# Dx32_V1_1.net
KiCad netlist of a schematic drawn in EAGLE
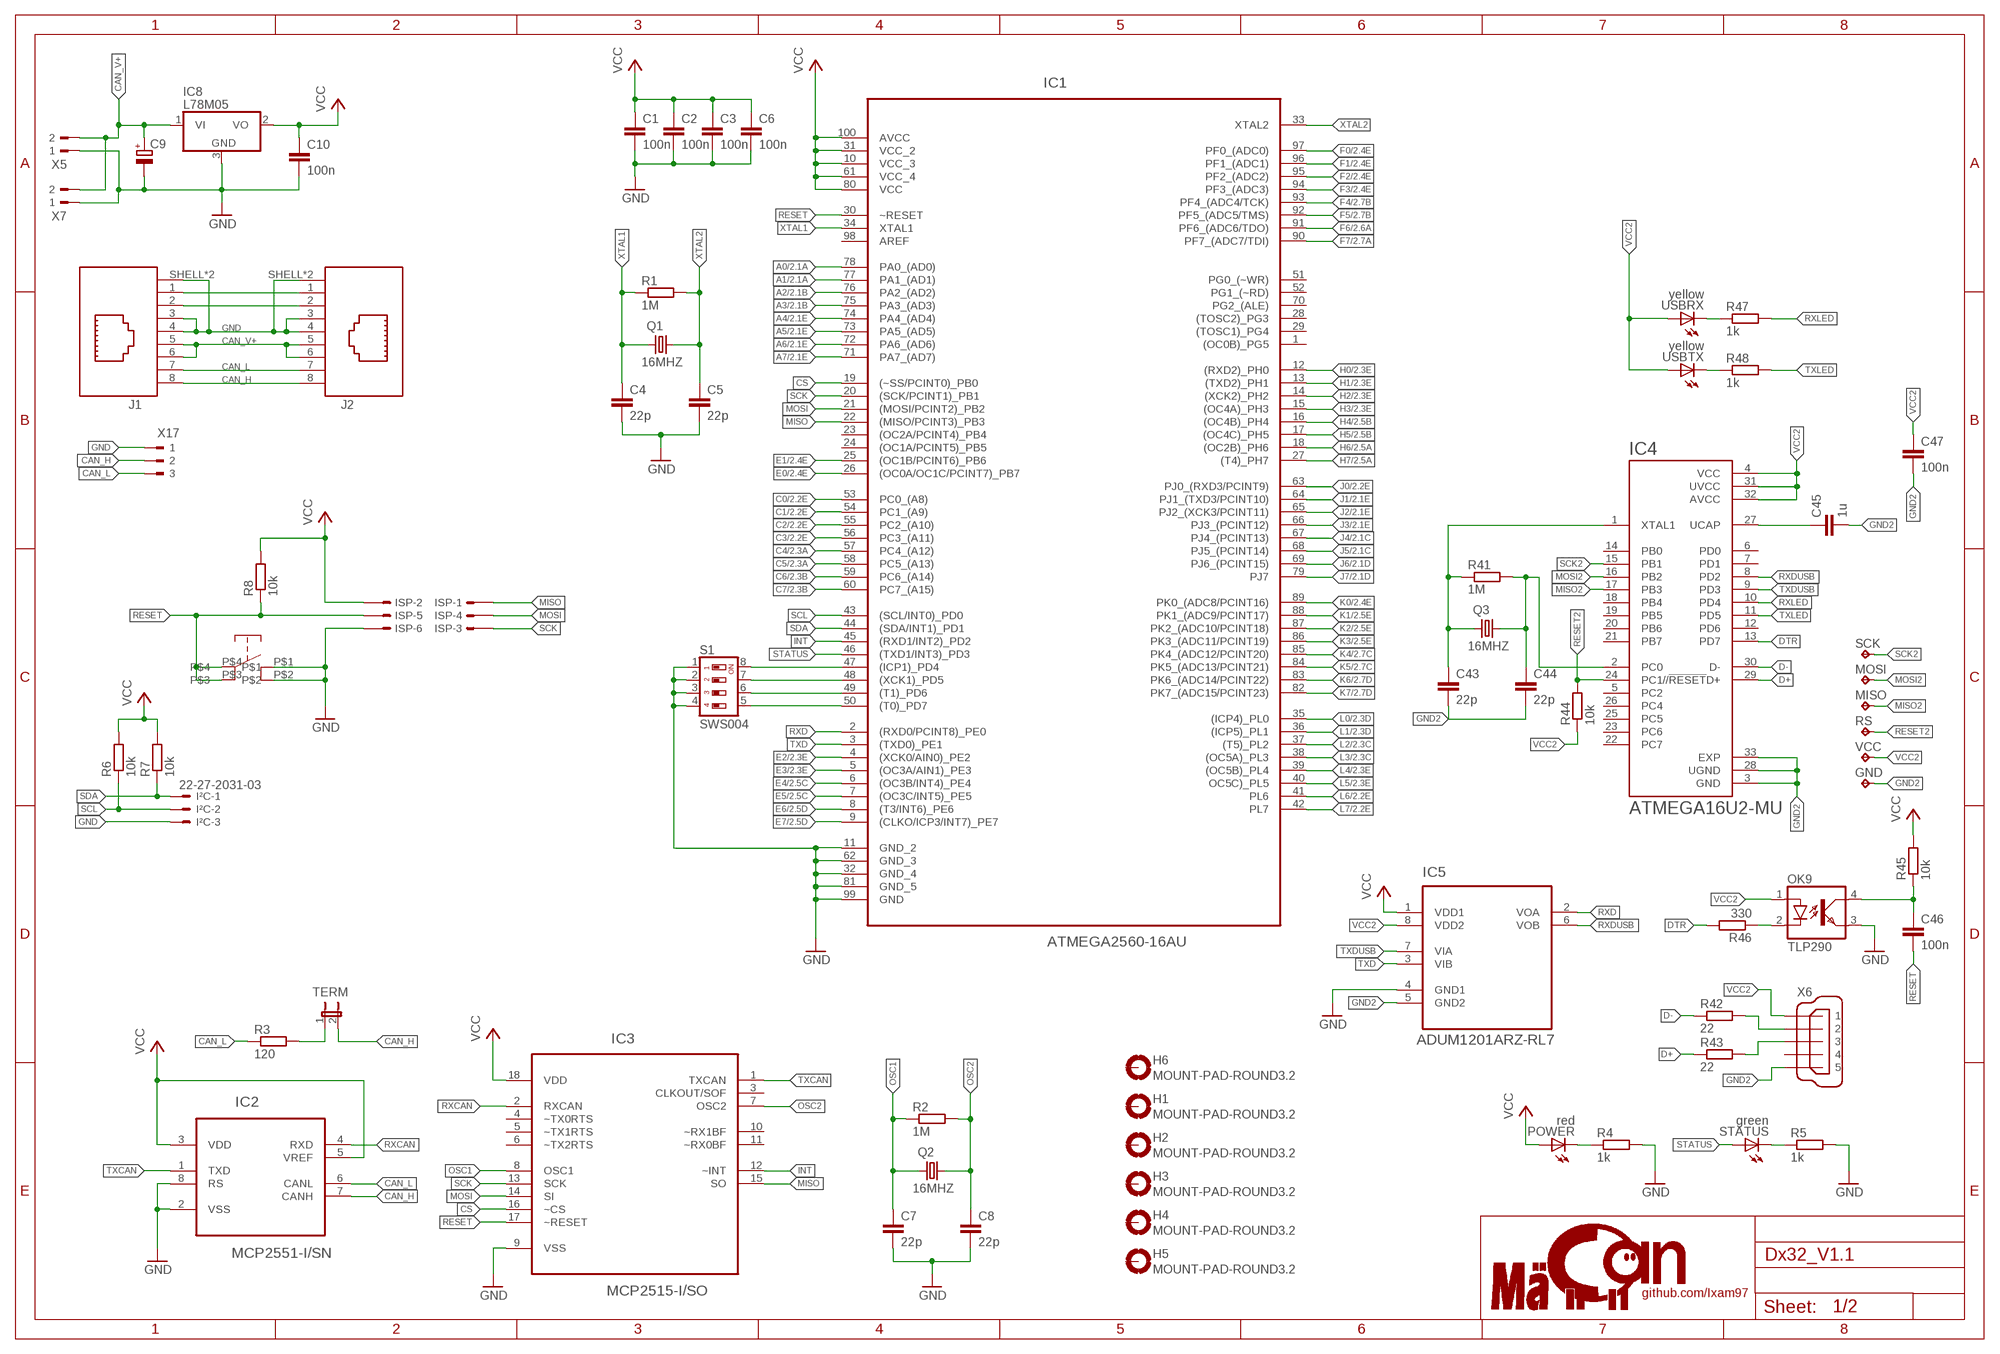
[diagram p0: schematic, sheet 1]
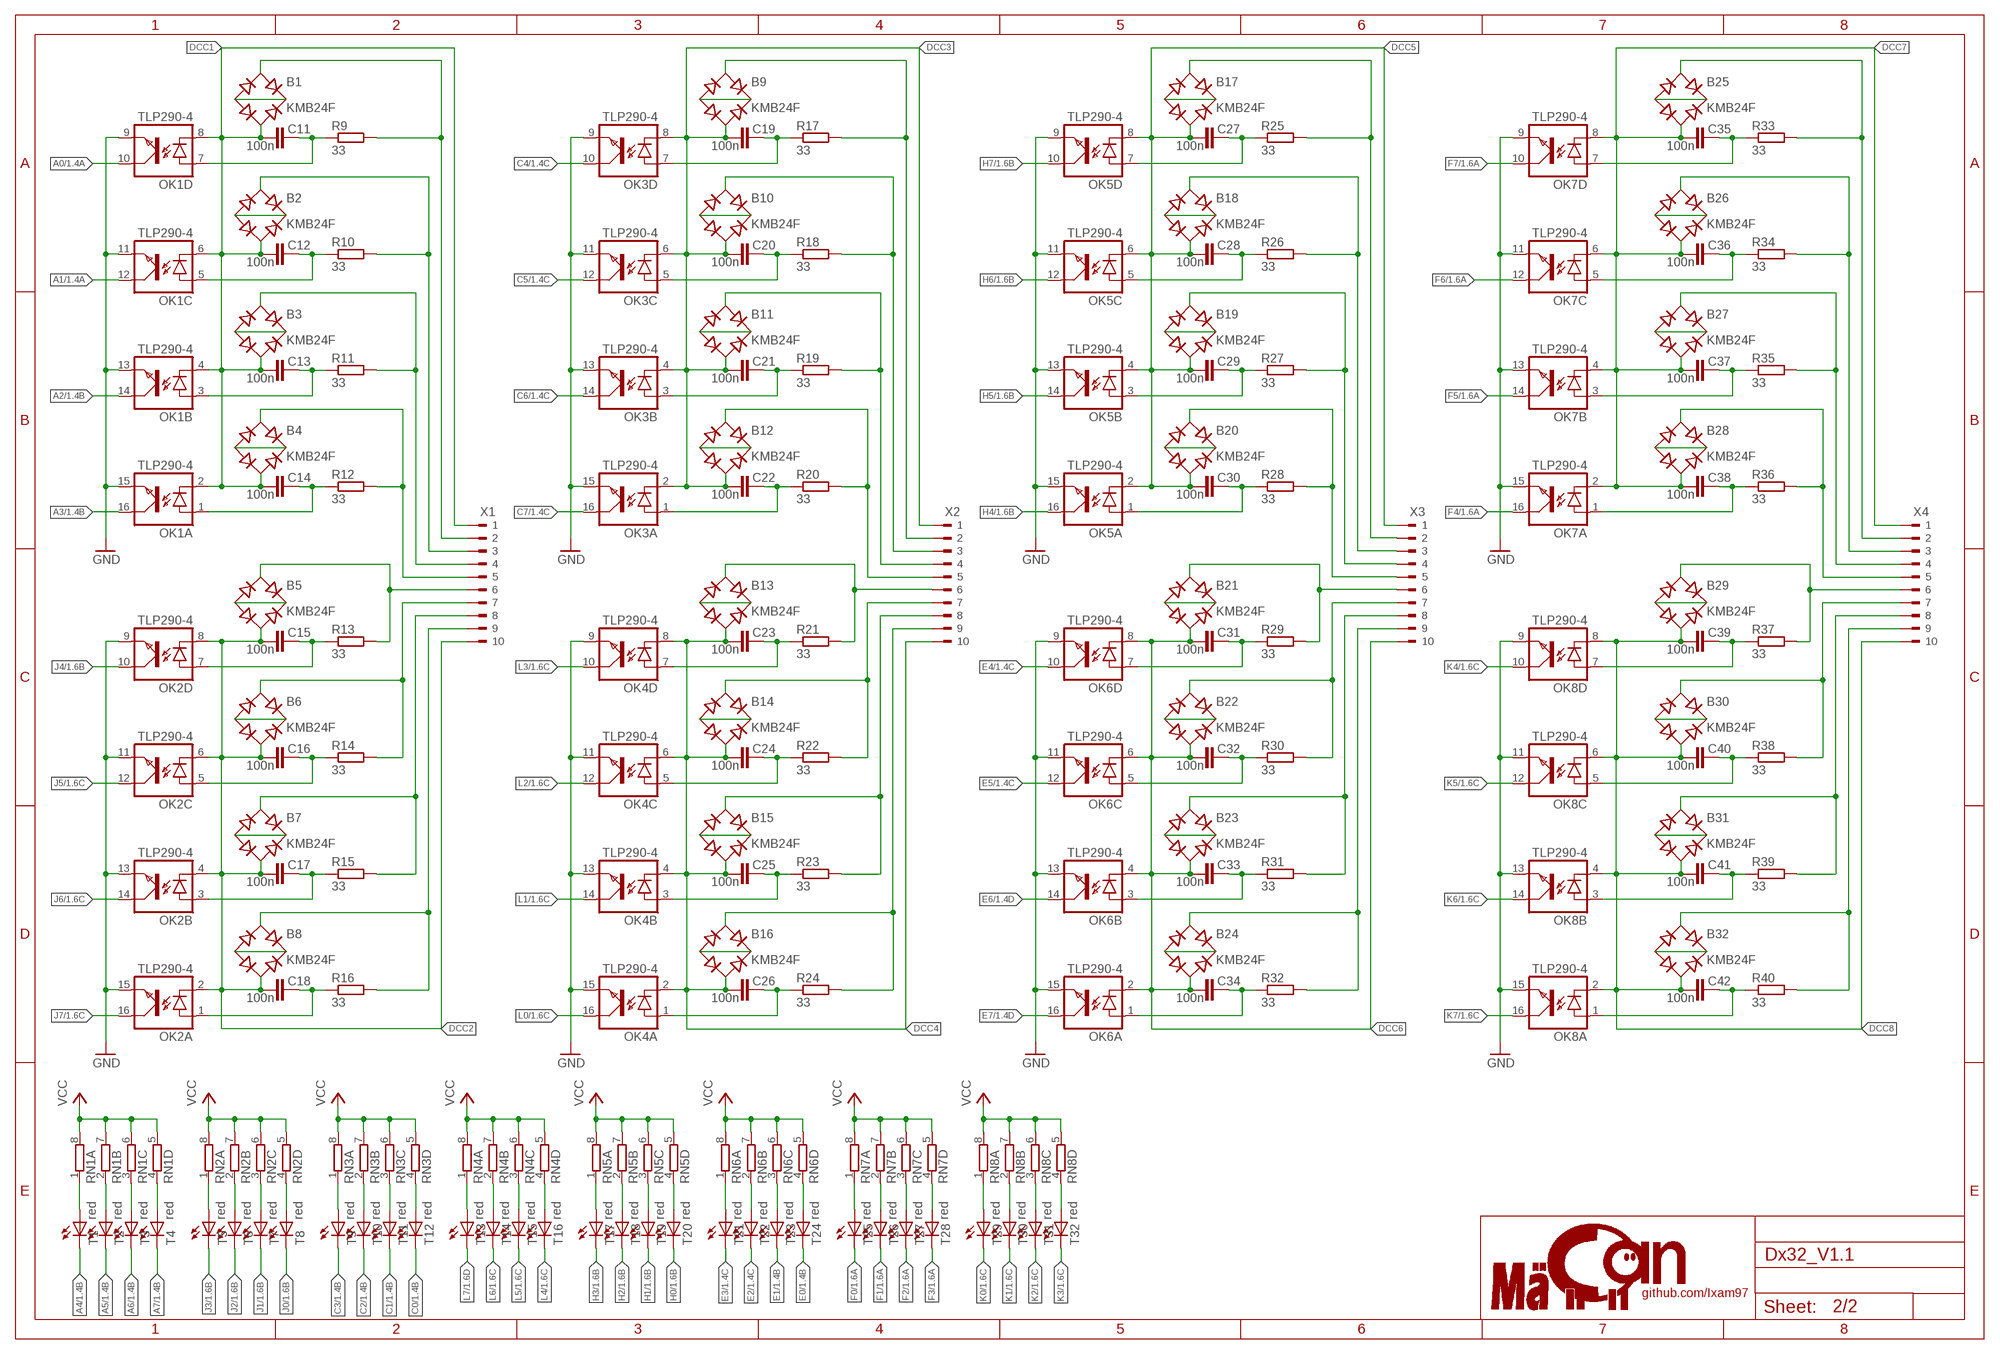
[diagram p1: schematic, sheet 2]

(export (version "E")
  (design (tool "Eeschema 10.0.6"))
  (components
    (comp (ref "B1")
      (value "KMB24F")
      (footprint "eagle-import:MBS")
      (fields (field (name "JLCPCB-PART") "C113927"))
      (libsource (lib "eagle-import") (part "BS2"))
    )
    (comp (ref "B2")
      (value "KMB24F")
      (footprint "eagle-import:MBS")
      (libsource (lib "eagle-import") (part "BS2"))
    )
    (comp (ref "B3")
      (value "KMB24F")
      (footprint "eagle-import:MBS")
      (libsource (lib "eagle-import") (part "BS2"))
    )
    (comp (ref "B4")
      (value "KMB24F")
      (footprint "eagle-import:MBS")
      (libsource (lib "eagle-import") (part "BS2"))
    )
    (comp (ref "B5")
      (value "KMB24F")
      (footprint "eagle-import:MBS")
      (libsource (lib "eagle-import") (part "BS2"))
    )
    (comp (ref "B6")
      (value "KMB24F")
      (footprint "eagle-import:MBS")
      (libsource (lib "eagle-import") (part "BS2"))
    )
    (comp (ref "B7")
      (value "KMB24F")
      (footprint "eagle-import:MBS")
      (libsource (lib "eagle-import") (part "BS2"))
    )
    (comp (ref "B8")
      (value "KMB24F")
      (footprint "eagle-import:MBS")
      (libsource (lib "eagle-import") (part "BS2"))
    )
    (comp (ref "B9")
      (value "KMB24F")
      (footprint "eagle-import:MBS")
      (libsource (lib "eagle-import") (part "BS2"))
    )
    (comp (ref "B10")
      (value "KMB24F")
      (footprint "eagle-import:MBS")
      (libsource (lib "eagle-import") (part "BS2"))
    )
    (comp (ref "B11")
      (value "KMB24F")
      (footprint "eagle-import:MBS")
      (libsource (lib "eagle-import") (part "BS2"))
    )
    (comp (ref "B12")
      (value "KMB24F")
      (footprint "eagle-import:MBS")
      (libsource (lib "eagle-import") (part "BS2"))
    )
    (comp (ref "B13")
      (value "KMB24F")
      (footprint "eagle-import:MBS")
      (libsource (lib "eagle-import") (part "BS2"))
    )
    (comp (ref "B14")
      (value "KMB24F")
      (footprint "eagle-import:MBS")
      (libsource (lib "eagle-import") (part "BS2"))
    )
    (comp (ref "B15")
      (value "KMB24F")
      (footprint "eagle-import:MBS")
      (libsource (lib "eagle-import") (part "BS2"))
    )
    (comp (ref "B16")
      (value "KMB24F")
      (footprint "eagle-import:MBS")
      (libsource (lib "eagle-import") (part "BS2"))
    )
    (comp (ref "B17")
      (value "KMB24F")
      (footprint "eagle-import:MBS")
      (libsource (lib "eagle-import") (part "BS2"))
    )
    (comp (ref "B18")
      (value "KMB24F")
      (footprint "eagle-import:MBS")
      (libsource (lib "eagle-import") (part "BS2"))
    )
    (comp (ref "B19")
      (value "KMB24F")
      (footprint "eagle-import:MBS")
      (libsource (lib "eagle-import") (part "BS2"))
    )
    (comp (ref "B20")
      (value "KMB24F")
      (footprint "eagle-import:MBS")
      (libsource (lib "eagle-import") (part "BS2"))
    )
    (comp (ref "B21")
      (value "KMB24F")
      (footprint "eagle-import:MBS")
      (libsource (lib "eagle-import") (part "BS2"))
    )
    (comp (ref "B22")
      (value "KMB24F")
      (footprint "eagle-import:MBS")
      (libsource (lib "eagle-import") (part "BS2"))
    )
    (comp (ref "B23")
      (value "KMB24F")
      (footprint "eagle-import:MBS")
      (libsource (lib "eagle-import") (part "BS2"))
    )
    (comp (ref "B24")
      (value "KMB24F")
      (footprint "eagle-import:MBS")
      (libsource (lib "eagle-import") (part "BS2"))
    )
    (comp (ref "B25")
      (value "KMB24F")
      (footprint "eagle-import:MBS")
      (libsource (lib "eagle-import") (part "BS2"))
    )
    (comp (ref "B26")
      (value "KMB24F")
      (footprint "eagle-import:MBS")
      (libsource (lib "eagle-import") (part "BS2"))
    )
    (comp (ref "B27")
      (value "KMB24F")
      (footprint "eagle-import:MBS")
      (libsource (lib "eagle-import") (part "BS2"))
    )
    (comp (ref "B28")
      (value "KMB24F")
      (footprint "eagle-import:MBS")
      (libsource (lib "eagle-import") (part "BS2"))
    )
    (comp (ref "B29")
      (value "KMB24F")
      (footprint "eagle-import:MBS")
      (libsource (lib "eagle-import") (part "BS2"))
    )
    (comp (ref "B30")
      (value "KMB24F")
      (footprint "eagle-import:MBS")
      (libsource (lib "eagle-import") (part "BS2"))
    )
    (comp (ref "B31")
      (value "KMB24F")
      (footprint "eagle-import:MBS")
      (libsource (lib "eagle-import") (part "BS2"))
    )
    (comp (ref "B32")
      (value "KMB24F")
      (footprint "eagle-import:MBS")
      (libsource (lib "eagle-import") (part "BS2"))
    )
    (comp (ref "C11")
      (value "100n")
      (footprint "eagle-import:C0402")
      (libsource (lib "eagle-import") (part "C-EUC0402"))
    )
    (comp (ref "C12")
      (value "100n")
      (footprint "eagle-import:C0402")
      (libsource (lib "eagle-import") (part "C-EUC0402"))
    )
    (comp (ref "C13")
      (value "100n")
      (footprint "eagle-import:C0402")
      (libsource (lib "eagle-import") (part "C-EUC0402"))
    )
    (comp (ref "C14")
      (value "100n")
      (footprint "eagle-import:C0402")
      (libsource (lib "eagle-import") (part "C-EUC0402"))
    )
    (comp (ref "C15")
      (value "100n")
      (footprint "eagle-import:C0402")
      (libsource (lib "eagle-import") (part "C-EUC0402"))
    )
    (comp (ref "C16")
      (value "100n")
      (footprint "eagle-import:C0402")
      (libsource (lib "eagle-import") (part "C-EUC0402"))
    )
    (comp (ref "C17")
      (value "100n")
      (footprint "eagle-import:C0402")
      (libsource (lib "eagle-import") (part "C-EUC0402"))
    )
    (comp (ref "C18")
      (value "100n")
      (footprint "eagle-import:C0402")
      (libsource (lib "eagle-import") (part "C-EUC0402"))
    )
    (comp (ref "C19")
      (value "100n")
      (footprint "eagle-import:C0402")
      (libsource (lib "eagle-import") (part "C-EUC0402"))
    )
    (comp (ref "C20")
      (value "100n")
      (footprint "eagle-import:C0402")
      (libsource (lib "eagle-import") (part "C-EUC0402"))
    )
    (comp (ref "C21")
      (value "100n")
      (footprint "eagle-import:C0402")
      (libsource (lib "eagle-import") (part "C-EUC0402"))
    )
    (comp (ref "C22")
      (value "100n")
      (footprint "eagle-import:C0402")
      (libsource (lib "eagle-import") (part "C-EUC0402"))
    )
    (comp (ref "C23")
      (value "100n")
      (footprint "eagle-import:C0402")
      (libsource (lib "eagle-import") (part "C-EUC0402"))
    )
    (comp (ref "C24")
      (value "100n")
      (footprint "eagle-import:C0402")
      (libsource (lib "eagle-import") (part "C-EUC0402"))
    )
    (comp (ref "C25")
      (value "100n")
      (footprint "eagle-import:C0402")
      (libsource (lib "eagle-import") (part "C-EUC0402"))
    )
    (comp (ref "C26")
      (value "100n")
      (footprint "eagle-import:C0402")
      (libsource (lib "eagle-import") (part "C-EUC0402"))
    )
    (comp (ref "C27")
      (value "100n")
      (footprint "eagle-import:C0402")
      (libsource (lib "eagle-import") (part "C-EUC0402"))
    )
    (comp (ref "C28")
      (value "100n")
      (footprint "eagle-import:C0402")
      (libsource (lib "eagle-import") (part "C-EUC0402"))
    )
    (comp (ref "C29")
      (value "100n")
      (footprint "eagle-import:C0402")
      (libsource (lib "eagle-import") (part "C-EUC0402"))
    )
    (comp (ref "C30")
      (value "100n")
      (footprint "eagle-import:C0402")
      (libsource (lib "eagle-import") (part "C-EUC0402"))
    )
    (comp (ref "C31")
      (value "100n")
      (footprint "eagle-import:C0402")
      (libsource (lib "eagle-import") (part "C-EUC0402"))
    )
    (comp (ref "C32")
      (value "100n")
      (footprint "eagle-import:C0402")
      (libsource (lib "eagle-import") (part "C-EUC0402"))
    )
    (comp (ref "C33")
      (value "100n")
      (footprint "eagle-import:C0402")
      (libsource (lib "eagle-import") (part "C-EUC0402"))
    )
    (comp (ref "C34")
      (value "100n")
      (footprint "eagle-import:C0402")
      (libsource (lib "eagle-import") (part "C-EUC0402"))
    )
    (comp (ref "C35")
      (value "100n")
      (footprint "eagle-import:C0402")
      (libsource (lib "eagle-import") (part "C-EUC0402"))
    )
    (comp (ref "C36")
      (value "100n")
      (footprint "eagle-import:C0402")
      (libsource (lib "eagle-import") (part "C-EUC0402"))
    )
    (comp (ref "C37")
      (value "100n")
      (footprint "eagle-import:C0402")
      (libsource (lib "eagle-import") (part "C-EUC0402"))
    )
    (comp (ref "C38")
      (value "100n")
      (footprint "eagle-import:C0402")
      (libsource (lib "eagle-import") (part "C-EUC0402"))
    )
    (comp (ref "C39")
      (value "100n")
      (footprint "eagle-import:C0402")
      (libsource (lib "eagle-import") (part "C-EUC0402"))
    )
    (comp (ref "C40")
      (value "100n")
      (footprint "eagle-import:C0402")
      (libsource (lib "eagle-import") (part "C-EUC0402"))
    )
    (comp (ref "C41")
      (value "100n")
      (footprint "eagle-import:C0402")
      (libsource (lib "eagle-import") (part "C-EUC0402"))
    )
    (comp (ref "C42")
      (value "100n")
      (footprint "eagle-import:C0402")
      (libsource (lib "eagle-import") (part "C-EUC0402"))
    )
    (comp (ref "OK1")
      (value "TLP290-4")
      (footprint "eagle-import:MINI-FLAT-16")
      (fields (field (name "JLCPC-PART") "C39031"))
      (libsource (lib "eagle-import") (part "TLP283-4"))
    )
    (comp (ref "OK2")
      (value "TLP290-4")
      (footprint "eagle-import:MINI-FLAT-16")
      (libsource (lib "eagle-import") (part "TLP283-4"))
    )
    (comp (ref "OK3")
      (value "TLP290-4")
      (footprint "eagle-import:MINI-FLAT-16")
      (libsource (lib "eagle-import") (part "TLP283-4"))
    )
    (comp (ref "OK4")
      (value "TLP290-4")
      (footprint "eagle-import:MINI-FLAT-16")
      (libsource (lib "eagle-import") (part "TLP283-4"))
    )
    (comp (ref "OK5")
      (value "TLP290-4")
      (footprint "eagle-import:MINI-FLAT-16")
      (libsource (lib "eagle-import") (part "TLP283-4"))
    )
    (comp (ref "OK6")
      (value "TLP290-4")
      (footprint "eagle-import:MINI-FLAT-16")
      (libsource (lib "eagle-import") (part "TLP283-4"))
    )
    (comp (ref "OK7")
      (value "TLP290-4")
      (footprint "eagle-import:MINI-FLAT-16")
      (libsource (lib "eagle-import") (part "TLP283-4"))
    )
    (comp (ref "OK8")
      (value "TLP290-4")
      (footprint "eagle-import:MINI-FLAT-16")
      (libsource (lib "eagle-import") (part "TLP283-4"))
    )
    (comp (ref "R9")
      (value "33")
      (footprint "eagle-import:R0402")
      (libsource (lib "eagle-import") (part "R-EU_R0402"))
    )
    (comp (ref "R10")
      (value "33")
      (footprint "eagle-import:R0402")
      (libsource (lib "eagle-import") (part "R-EU_R0402"))
    )
    (comp (ref "R11")
      (value "33")
      (footprint "eagle-import:R0402")
      (libsource (lib "eagle-import") (part "R-EU_R0402"))
    )
    (comp (ref "R12")
      (value "33")
      (footprint "eagle-import:R0402")
      (libsource (lib "eagle-import") (part "R-EU_R0402"))
    )
    (comp (ref "R13")
      (value "33")
      (footprint "eagle-import:R0402")
      (libsource (lib "eagle-import") (part "R-EU_R0402"))
    )
    (comp (ref "R14")
      (value "33")
      (footprint "eagle-import:R0402")
      (libsource (lib "eagle-import") (part "R-EU_R0402"))
    )
    (comp (ref "R15")
      (value "33")
      (footprint "eagle-import:R0402")
      (libsource (lib "eagle-import") (part "R-EU_R0402"))
    )
    (comp (ref "R16")
      (value "33")
      (footprint "eagle-import:R0402")
      (libsource (lib "eagle-import") (part "R-EU_R0402"))
    )
    (comp (ref "R17")
      (value "33")
      (footprint "eagle-import:R0402")
      (libsource (lib "eagle-import") (part "R-EU_R0402"))
    )
    (comp (ref "R18")
      (value "33")
      (footprint "eagle-import:R0402")
      (libsource (lib "eagle-import") (part "R-EU_R0402"))
    )
    (comp (ref "R19")
      (value "33")
      (footprint "eagle-import:R0402")
      (libsource (lib "eagle-import") (part "R-EU_R0402"))
    )
    (comp (ref "R20")
      (value "33")
      (footprint "eagle-import:R0402")
      (libsource (lib "eagle-import") (part "R-EU_R0402"))
    )
    (comp (ref "R21")
      (value "33")
      (footprint "eagle-import:R0402")
      (libsource (lib "eagle-import") (part "R-EU_R0402"))
    )
    (comp (ref "R22")
      (value "33")
      (footprint "eagle-import:R0402")
      (libsource (lib "eagle-import") (part "R-EU_R0402"))
    )
    (comp (ref "R23")
      (value "33")
      (footprint "eagle-import:R0402")
      (libsource (lib "eagle-import") (part "R-EU_R0402"))
    )
    (comp (ref "R24")
      (value "33")
      (footprint "eagle-import:R0402")
      (libsource (lib "eagle-import") (part "R-EU_R0402"))
    )
    (comp (ref "R25")
      (value "33")
      (footprint "eagle-import:R0402")
      (libsource (lib "eagle-import") (part "R-EU_R0402"))
    )
    (comp (ref "R26")
      (value "33")
      (footprint "eagle-import:R0402")
      (libsource (lib "eagle-import") (part "R-EU_R0402"))
    )
    (comp (ref "R27")
      (value "33")
      (footprint "eagle-import:R0402")
      (libsource (lib "eagle-import") (part "R-EU_R0402"))
    )
    (comp (ref "R28")
      (value "33")
      (footprint "eagle-import:R0402")
      (libsource (lib "eagle-import") (part "R-EU_R0402"))
    )
    (comp (ref "R29")
      (value "33")
      (footprint "eagle-import:R0402")
      (libsource (lib "eagle-import") (part "R-EU_R0402"))
    )
    (comp (ref "R30")
      (value "33")
      (footprint "eagle-import:R0402")
      (libsource (lib "eagle-import") (part "R-EU_R0402"))
    )
    (comp (ref "R31")
      (value "33")
      (footprint "eagle-import:R0402")
      (libsource (lib "eagle-import") (part "R-EU_R0402"))
    )
    (comp (ref "R32")
      (value "33")
      (footprint "eagle-import:R0402")
      (libsource (lib "eagle-import") (part "R-EU_R0402"))
    )
    (comp (ref "R33")
      (value "33")
      (footprint "eagle-import:R0402")
      (libsource (lib "eagle-import") (part "R-EU_R0402"))
    )
    (comp (ref "R34")
      (value "33")
      (footprint "eagle-import:R0402")
      (libsource (lib "eagle-import") (part "R-EU_R0402"))
    )
    (comp (ref "R35")
      (value "33")
      (footprint "eagle-import:R0402")
      (libsource (lib "eagle-import") (part "R-EU_R0402"))
    )
    (comp (ref "R36")
      (value "33")
      (footprint "eagle-import:R0402")
      (libsource (lib "eagle-import") (part "R-EU_R0402"))
    )
    (comp (ref "R37")
      (value "33")
      (footprint "eagle-import:R0402")
      (libsource (lib "eagle-import") (part "R-EU_R0402"))
    )
    (comp (ref "R38")
      (value "33")
      (footprint "eagle-import:R0402")
      (libsource (lib "eagle-import") (part "R-EU_R0402"))
    )
    (comp (ref "R39")
      (value "33")
      (footprint "eagle-import:R0402")
      (libsource (lib "eagle-import") (part "R-EU_R0402"))
    )
    (comp (ref "R40")
      (value "33")
      (footprint "eagle-import:R0402")
      (libsource (lib "eagle-import") (part "R-EU_R0402"))
    )
    (comp (ref "RN1")
      (value "4R-N0603-ARV")
      (footprint "eagle-import:0603-ARV")
      (libsource (lib "eagle-import") (part "4R-N0603-ARV"))
    )
    (comp (ref "RN2")
      (value "4R-N0603-ARV")
      (footprint "eagle-import:0603-ARV")
      (libsource (lib "eagle-import") (part "4R-N0603-ARV"))
    )
    (comp (ref "RN3")
      (value "4R-N0603-ARV")
      (footprint "eagle-import:0603-ARV")
      (libsource (lib "eagle-import") (part "4R-N0603-ARV"))
    )
    (comp (ref "RN4")
      (value "4R-N0603-ARV")
      (footprint "eagle-import:0603-ARV")
      (libsource (lib "eagle-import") (part "4R-N0603-ARV"))
    )
    (comp (ref "RN5")
      (value "4R-N0603-ARV")
      (footprint "eagle-import:0603-ARV")
      (libsource (lib "eagle-import") (part "4R-N0603-ARV"))
    )
    (comp (ref "RN6")
      (value "4R-N0603-ARV")
      (footprint "eagle-import:0603-ARV")
      (libsource (lib "eagle-import") (part "4R-N0603-ARV"))
    )
    (comp (ref "RN7")
      (value "4R-N0603-ARV")
      (footprint "eagle-import:0603-ARV")
      (libsource (lib "eagle-import") (part "4R-N0603-ARV"))
    )
    (comp (ref "RN8")
      (value "4R-N0603-ARV")
      (footprint "eagle-import:0603-ARV")
      (libsource (lib "eagle-import") (part "4R-N0603-ARV"))
    )
    (comp (ref "T1")
      (value "red")
      (footprint "eagle-import:CHIP-LED0805")
      (fields (field (name "JLCPCB-PART") "C84256"))
      (libsource (lib "eagle-import") (part "LEDCHIP-LED0805"))
    )
    (comp (ref "T2")
      (value "red")
      (footprint "eagle-import:CHIP-LED0805")
      (libsource (lib "eagle-import") (part "LEDCHIP-LED0805"))
    )
    (comp (ref "T3")
      (value "red")
      (footprint "eagle-import:CHIP-LED0805")
      (libsource (lib "eagle-import") (part "LEDCHIP-LED0805"))
    )
    (comp (ref "T4")
      (value "red")
      (footprint "eagle-import:CHIP-LED0805")
      (libsource (lib "eagle-import") (part "LEDCHIP-LED0805"))
    )
    (comp (ref "T5")
      (value "red")
      (footprint "eagle-import:CHIP-LED0805")
      (libsource (lib "eagle-import") (part "LEDCHIP-LED0805"))
    )
    (comp (ref "T6")
      (value "red")
      (footprint "eagle-import:CHIP-LED0805")
      (libsource (lib "eagle-import") (part "LEDCHIP-LED0805"))
    )
    (comp (ref "T7")
      (value "red")
      (footprint "eagle-import:CHIP-LED0805")
      (libsource (lib "eagle-import") (part "LEDCHIP-LED0805"))
    )
    (comp (ref "T8")
      (value "red")
      (footprint "eagle-import:CHIP-LED0805")
      (libsource (lib "eagle-import") (part "LEDCHIP-LED0805"))
    )
    (comp (ref "T9")
      (value "red")
      (footprint "eagle-import:CHIP-LED0805")
      (libsource (lib "eagle-import") (part "LEDCHIP-LED0805"))
    )
    (comp (ref "T10")
      (value "red")
      (footprint "eagle-import:CHIP-LED0805")
      (libsource (lib "eagle-import") (part "LEDCHIP-LED0805"))
    )
    (comp (ref "T11")
      (value "red")
      (footprint "eagle-import:CHIP-LED0805")
      (libsource (lib "eagle-import") (part "LEDCHIP-LED0805"))
    )
    (comp (ref "T12")
      (value "red")
      (footprint "eagle-import:CHIP-LED0805")
      (libsource (lib "eagle-import") (part "LEDCHIP-LED0805"))
    )
    (comp (ref "T13")
      (value "red")
      (footprint "eagle-import:CHIP-LED0805")
      (libsource (lib "eagle-import") (part "LEDCHIP-LED0805"))
    )
    (comp (ref "T14")
      (value "red")
      (footprint "eagle-import:CHIP-LED0805")
      (libsource (lib "eagle-import") (part "LEDCHIP-LED0805"))
    )
    (comp (ref "T15")
      (value "red")
      (footprint "eagle-import:CHIP-LED0805")
      (libsource (lib "eagle-import") (part "LEDCHIP-LED0805"))
    )
    (comp (ref "T16")
      (value "red")
      (footprint "eagle-import:CHIP-LED0805")
      (libsource (lib "eagle-import") (part "LEDCHIP-LED0805"))
    )
    (comp (ref "T17")
      (value "red")
      (footprint "eagle-import:CHIP-LED0805")
      (libsource (lib "eagle-import") (part "LEDCHIP-LED0805"))
    )
    (comp (ref "T18")
      (value "red")
      (footprint "eagle-import:CHIP-LED0805")
      (libsource (lib "eagle-import") (part "LEDCHIP-LED0805"))
    )
    (comp (ref "T19")
      (value "red")
      (footprint "eagle-import:CHIP-LED0805")
      (libsource (lib "eagle-import") (part "LEDCHIP-LED0805"))
    )
    (comp (ref "T20")
      (value "red")
      (footprint "eagle-import:CHIP-LED0805")
      (libsource (lib "eagle-import") (part "LEDCHIP-LED0805"))
    )
    (comp (ref "T21")
      (value "red")
      (footprint "eagle-import:CHIP-LED0805")
      (libsource (lib "eagle-import") (part "LEDCHIP-LED0805"))
    )
    (comp (ref "T22")
      (value "red")
      (footprint "eagle-import:CHIP-LED0805")
      (libsource (lib "eagle-import") (part "LEDCHIP-LED0805"))
    )
    (comp (ref "T23")
      (value "red")
      (footprint "eagle-import:CHIP-LED0805")
      (libsource (lib "eagle-import") (part "LEDCHIP-LED0805"))
    )
    (comp (ref "T24")
      (value "red")
      (footprint "eagle-import:CHIP-LED0805")
      (libsource (lib "eagle-import") (part "LEDCHIP-LED0805"))
    )
    (comp (ref "T25")
      (value "red")
      (footprint "eagle-import:CHIP-LED0805")
      (libsource (lib "eagle-import") (part "LEDCHIP-LED0805"))
    )
    (comp (ref "T26")
      (value "red")
      (footprint "eagle-import:CHIP-LED0805")
      (libsource (lib "eagle-import") (part "LEDCHIP-LED0805"))
    )
    (comp (ref "T27")
      (value "red")
      (footprint "eagle-import:CHIP-LED0805")
      (libsource (lib "eagle-import") (part "LEDCHIP-LED0805"))
    )
    (comp (ref "T28")
      (value "red")
      (footprint "eagle-import:CHIP-LED0805")
      (libsource (lib "eagle-import") (part "LEDCHIP-LED0805"))
    )
    (comp (ref "T29")
      (value "red")
      (footprint "eagle-import:CHIP-LED0805")
      (libsource (lib "eagle-import") (part "LEDCHIP-LED0805"))
    )
    (comp (ref "T30")
      (value "red")
      (footprint "eagle-import:CHIP-LED0805")
      (libsource (lib "eagle-import") (part "LEDCHIP-LED0805"))
    )
    (comp (ref "T31")
      (value "red")
      (footprint "eagle-import:CHIP-LED0805")
      (libsource (lib "eagle-import") (part "LEDCHIP-LED0805"))
    )
    (comp (ref "T32")
      (value "red")
      (footprint "eagle-import:CHIP-LED0805")
      (libsource (lib "eagle-import") (part "LEDCHIP-LED0805"))
    )
    (comp (ref "X1")
      (value "180-10")
      (footprint "eagle-import:180-10")
      (libsource (lib "eagle-import") (part "180-10"))
    )
    (comp (ref "X2")
      (value "180-10")
      (footprint "eagle-import:180-10")
      (libsource (lib "eagle-import") (part "180-10"))
    )
    (comp (ref "X3")
      (value "180-10")
      (footprint "eagle-import:180-10")
      (libsource (lib "eagle-import") (part "180-10"))
    )
    (comp (ref "X4")
      (value "180-10")
      (footprint "eagle-import:180-10")
      (libsource (lib "eagle-import") (part "180-10"))
    )
    (comp (ref "C1")
      (value "100n")
      (footprint "eagle-import:C0402")
      (libsource (lib "eagle-import") (part "C-EUC0402"))
    )
    (comp (ref "C2")
      (value "100n")
      (footprint "eagle-import:C0402")
      (libsource (lib "eagle-import") (part "C-EUC0402"))
    )
    (comp (ref "C3")
      (value "100n")
      (footprint "eagle-import:C0402")
      (libsource (lib "eagle-import") (part "C-EUC0402"))
    )
    (comp (ref "C4")
      (value "22p")
      (footprint "eagle-import:C0402")
      (libsource (lib "eagle-import") (part "C-EUC0402"))
    )
    (comp (ref "C5")
      (value "22p")
      (footprint "eagle-import:C0402")
      (libsource (lib "eagle-import") (part "C-EUC0402"))
    )
    (comp (ref "C6")
      (value "100n")
      (footprint "eagle-import:C0402")
      (libsource (lib "eagle-import") (part "C-EUC0402"))
    )
    (comp (ref "C7")
      (value "22p")
      (footprint "eagle-import:C0402")
      (libsource (lib "eagle-import") (part "C-EUC0402"))
    )
    (comp (ref "C8")
      (value "22p")
      (footprint "eagle-import:C0402")
      (libsource (lib "eagle-import") (part "C-EUC0402"))
    )
    (comp (ref "C9")
      (value "CPOL-EUCT3216")
      (footprint "eagle-import:CT3216")
      (libsource (lib "eagle-import") (part "CPOL-EUCT3216"))
    )
    (comp (ref "C10")
      (value "100n")
      (footprint "eagle-import:C0402")
      (libsource (lib "eagle-import") (part "C-EUC0402"))
    )
    (comp (ref "C43")
      (value "22p")
      (footprint "eagle-import:C0402")
      (libsource (lib "eagle-import") (part "C-EUC0402"))
    )
    (comp (ref "C44")
      (value "22p")
      (footprint "eagle-import:C0402")
      (libsource (lib "eagle-import") (part "C-EUC0402"))
    )
    (comp (ref "C45")
      (value "1u")
      (footprint "eagle-import:C0402")
      (libsource (lib "eagle-import") (part "C-EUC0402"))
    )
    (comp (ref "C46")
      (value "100n")
      (footprint "eagle-import:C0402")
      (libsource (lib "eagle-import") (part "C-EUC0402"))
    )
    (comp (ref "C47")
      (value "100n")
      (footprint "eagle-import:C0402")
      (libsource (lib "eagle-import") (part "C-EUC0402"))
    )
    (comp (ref "GND")
      (value "TPB1,27")
      (footprint "eagle-import:B1,27")
      (libsource (lib "eagle-import") (part "TPB1,27"))
    )
    (comp (ref "H1")
      (value "MOUNT-PAD-ROUND3.2")
      (footprint "eagle-import:3,2-PAD")
      (libsource (lib "eagle-import") (part "MOUNT-PAD-ROUND3.2"))
    )
    (comp (ref "H2")
      (value "MOUNT-PAD-ROUND3.2")
      (footprint "eagle-import:3,2-PAD")
      (libsource (lib "eagle-import") (part "MOUNT-PAD-ROUND3.2"))
    )
    (comp (ref "H3")
      (value "MOUNT-PAD-ROUND3.2")
      (footprint "eagle-import:3,2-PAD")
      (libsource (lib "eagle-import") (part "MOUNT-PAD-ROUND3.2"))
    )
    (comp (ref "H4")
      (value "MOUNT-PAD-ROUND3.2")
      (footprint "eagle-import:3,2-PAD")
      (libsource (lib "eagle-import") (part "MOUNT-PAD-ROUND3.2"))
    )
    (comp (ref "H5")
      (value "MOUNT-PAD-ROUND3.2")
      (footprint "eagle-import:3,2-PAD")
      (libsource (lib "eagle-import") (part "MOUNT-PAD-ROUND3.2"))
    )
    (comp (ref "H6")
      (value "MOUNT-PAD-ROUND3.2")
      (footprint "eagle-import:3,2-PAD")
      (libsource (lib "eagle-import") (part "MOUNT-PAD-ROUND3.2"))
    )
    (comp (ref "IC1")
      (value "ATMEGA2560-16AU")
      (footprint "eagle-import:QFP50P1600X1600X120-100N")
      (fields (field (name "MF") "Microchip"))
      (libsource (lib "eagle-import") (part "ATMEGA2560-16AU"))
    )
    (comp (ref "IC2")
      (value "MCP2551-I/SN")
      (footprint "eagle-import:SOIC127P600X175-8N")
      (libsource (lib "eagle-import") (part "MCP2551-I/SN"))
    )
    (comp (ref "IC3")
      (value "MCP2515-I/SO")
      (footprint "eagle-import:SOIC127P1034X264-18N")
      (libsource (lib "eagle-import") (part "MCP2515-I/SO"))
    )
    (comp (ref "IC4")
      (value "ATMEGA16U2-MU")
      (footprint "eagle-import:QFN50P500X500X100-33N")
      (fields (field (name "MF") "Microchip"))
      (libsource (lib "eagle-import") (part "ATMEGA16U2-MU"))
    )
    (comp (ref "IC5")
      (value "ADUM1201ARZ-RL7")
      (footprint "eagle-import:SOIC127P600X175-8N")
      (fields (field (name "MF") "Analog Devices"))
      (libsource (lib "eagle-import") (part "ADUM1201ARZ-RL7"))
    )
    (comp (ref "IC8")
      (value "L78M05")
      (footprint "eagle-import:TO252")
      (fields (field (name "JLCPCB-PART") "C58069"))
      (libsource (lib "eagle-import") (part "78DT05"))
    )
    (comp (ref "ISP")
      (value "057-006-1")
      (footprint "eagle-import:057-006-1")
      (libsource (lib "eagle-import") (part "057-006-1"))
    )
    (comp (ref "I²C")
      (value "22-27-2031-03")
      (footprint "eagle-import:6410-03")
      (fields (field (name "MF") "MOLEX"))
      (libsource (lib "eagle-import") (part "22-?-0327-2031"))
    )
    (comp (ref "J1")
      (value "615008140421")
      (footprint "eagle-import:615008140421")
      (libsource (lib "eagle-import") (part "615008140421"))
    )
    (comp (ref "J2")
      (value "615008140421")
      (footprint "eagle-import:615008140421")
      (libsource (lib "eagle-import") (part "615008140421"))
    )
    (comp (ref "MISO")
      (value "TPB1,27")
      (footprint "eagle-import:B1,27")
      (libsource (lib "eagle-import") (part "TPB1,27"))
    )
    (comp (ref "MOSI")
      (value "TPB1,27")
      (footprint "eagle-import:B1,27")
      (libsource (lib "eagle-import") (part "TPB1,27"))
    )
    (comp (ref "OK9")
      (value "TLP290")
      (footprint "eagle-import:MINI-FLAT-4")
      (libsource (lib "eagle-import") (part "TLP283"))
    )
    (comp (ref "POWER")
      (value "red")
      (footprint "eagle-import:CHIP-LED0805")
      (libsource (lib "eagle-import") (part "LEDCHIP-LED0805"))
    )
    (comp (ref "Q1")
      (value "16MHZ")
      (footprint "eagle-import:3.2X2.5_KX-7")
      (libsource (lib "eagle-import") (part "KX-7"))
    )
    (comp (ref "Q2")
      (value "16MHZ")
      (footprint "eagle-import:3.2X2.5_KX-7")
      (libsource (lib "eagle-import") (part "KX-7"))
    )
    (comp (ref "Q3")
      (value "16MHZ")
      (footprint "eagle-import:3.2X2.5_KX-7")
      (libsource (lib "eagle-import") (part "KX-7"))
    )
    (comp (ref "R1")
      (value "1M")
      (footprint "eagle-import:R0402")
      (libsource (lib "eagle-import") (part "R-EU_R0402"))
    )
    (comp (ref "R2")
      (value "1M")
      (footprint "eagle-import:R0402")
      (libsource (lib "eagle-import") (part "R-EU_R0402"))
    )
    (comp (ref "R3")
      (value "120")
      (footprint "eagle-import:R0402")
      (libsource (lib "eagle-import") (part "R-EU_R0402"))
    )
    (comp (ref "R4")
      (value "1k")
      (footprint "eagle-import:R0402")
      (libsource (lib "eagle-import") (part "R-EU_R0402"))
    )
    (comp (ref "R5")
      (value "1k")
      (footprint "eagle-import:R0402")
      (libsource (lib "eagle-import") (part "R-EU_R0402"))
    )
    (comp (ref "R6")
      (value "10k")
      (footprint "eagle-import:R0402")
      (libsource (lib "eagle-import") (part "R-EU_R0402"))
    )
    (comp (ref "R7")
      (value "10k")
      (footprint "eagle-import:R0402")
      (libsource (lib "eagle-import") (part "R-EU_R0402"))
    )
    (comp (ref "R8")
      (value "10k")
      (footprint "eagle-import:R0402")
      (libsource (lib "eagle-import") (part "R-EU_R0402"))
    )
    (comp (ref "R41")
      (value "1M")
      (footprint "eagle-import:R0402")
      (libsource (lib "eagle-import") (part "R-EU_R0402"))
    )
    (comp (ref "R42")
      (value "22")
      (footprint "eagle-import:R0402")
      (libsource (lib "eagle-import") (part "R-EU_R0402"))
    )
    (comp (ref "R43")
      (value "22")
      (footprint "eagle-import:R0402")
      (libsource (lib "eagle-import") (part "R-EU_R0402"))
    )
    (comp (ref "R44")
      (value "10k")
      (footprint "eagle-import:R0402")
      (libsource (lib "eagle-import") (part "R-EU_R0402"))
    )
    (comp (ref "R45")
      (value "10k")
      (footprint "eagle-import:R0402")
      (libsource (lib "eagle-import") (part "R-EU_R0402"))
    )
    (comp (ref "R46")
      (value "330")
      (footprint "eagle-import:R0402")
      (libsource (lib "eagle-import") (part "R-EU_R0402"))
    )
    (comp (ref "R47")
      (value "1k")
      (footprint "eagle-import:R0402")
      (libsource (lib "eagle-import") (part "R-EU_R0402"))
    )
    (comp (ref "R48")
      (value "1k")
      (footprint "eagle-import:R0402")
      (libsource (lib "eagle-import") (part "R-EU_R0402"))
    )
    (comp (ref "RS")
      (value "TPB1,27")
      (footprint "eagle-import:B1,27")
      (libsource (lib "eagle-import") (part "TPB1,27"))
    )
    (comp (ref "S1")
      (value "SWS004")
      (footprint "eagle-import:SMS-004")
      (libsource (lib "eagle-import") (part "SWS004"))
    )
    (comp (ref "SCK")
      (value "TPB1,27")
      (footprint "eagle-import:B1,27")
      (libsource (lib "eagle-import") (part "TPB1,27"))
    )
    (comp (ref "STATUS")
      (value "green")
      (footprint "eagle-import:CHIP-LED0805")
      (libsource (lib "eagle-import") (part "LEDCHIP-LED0805"))
    )
    (comp (ref "TERM")
      (value "JP1E")
      (footprint "eagle-import:JP1")
      (libsource (lib "eagle-import") (part "JP1E"))
    )
    (comp (ref "U$15")
      (value "BUTTON_JLC")
      (footprint "eagle-import:BUTTON")
      (libsource (lib "eagle-import") (part "BUTTON_JLC"))
    )
    (comp (ref "USBRX")
      (value "yellow")
      (footprint "eagle-import:CHIP-LED0805")
      (libsource (lib "eagle-import") (part "LEDCHIP-LED0805"))
    )
    (comp (ref "USBTX")
      (value "yellow")
      (footprint "eagle-import:CHIP-LED0805")
      (libsource (lib "eagle-import") (part "LEDCHIP-LED0805"))
    )
    (comp (ref "VCC")
      (value "TPB1,27")
      (footprint "eagle-import:B1,27")
      (libsource (lib "eagle-import") (part "TPB1,27"))
    )
    (comp (ref "X5")
      (value "180-2")
      (footprint "eagle-import:180-2")
      (libsource (lib "eagle-import") (part "180-2"))
    )
    (comp (ref "X6")
      (value "MINI-USB_SHIELD5P2-32005-601")
      (footprint "eagle-import:32005-601")
      (libsource (lib "eagle-import") (part "MINI-USB_SHIELD5P2-32005-601"))
    )
    (comp (ref "X7")
      (value "180-2")
      (footprint "eagle-import:180-2")
      (libsource (lib "eagle-import") (part "180-2"))
    )
    (comp (ref "X17")
      (value "180-3")
      (footprint "eagle-import:180-3")
      (libsource (lib "eagle-import") (part "180-3"))
    )
  )
  (nets
    (net (code "1") (name "A0") (class "Default")
      (node (ref "IC1") (pin "78") (pinfunction "PA0_(AD0)_78") (pintype "bidirectional"))
      (node (ref "OK1") (pin "10") (pinfunction "COL_10") (pintype "passive"))
    )
    (net (code "2") (name "A1") (class "Default")
      (node (ref "IC1") (pin "77") (pinfunction "PA1_(AD1)_77") (pintype "bidirectional"))
      (node (ref "OK1") (pin "12") (pinfunction "COL_12") (pintype "passive"))
    )
    (net (code "3") (name "A2") (class "Default")
      (node (ref "IC1") (pin "76") (pinfunction "PA2_(AD2)_76") (pintype "bidirectional"))
      (node (ref "OK1") (pin "14") (pinfunction "COL_14") (pintype "passive"))
    )
    (net (code "4") (name "A3") (class "Default")
      (node (ref "IC1") (pin "75") (pinfunction "PA3_(AD3)_75") (pintype "bidirectional"))
      (node (ref "OK1") (pin "16") (pinfunction "COL_16") (pintype "passive"))
    )
    (net (code "5") (name "A4") (class "Default")
      (node (ref "IC1") (pin "74") (pinfunction "PA4_(AD4)_74") (pintype "bidirectional"))
      (node (ref "T1") (pin "C") (pinfunction "C_C") (pintype "passive"))
    )
    (net (code "6") (name "A5") (class "Default")
      (node (ref "IC1") (pin "73") (pinfunction "PA5_(AD5)_73") (pintype "bidirectional"))
      (node (ref "T2") (pin "C") (pinfunction "C_C") (pintype "passive"))
    )
    (net (code "7") (name "A6") (class "Default")
      (node (ref "IC1") (pin "72") (pinfunction "PA6_(AD6)_72") (pintype "bidirectional"))
      (node (ref "T3") (pin "C") (pinfunction "C_C") (pintype "passive"))
    )
    (net (code "8") (name "A7") (class "Default")
      (node (ref "IC1") (pin "71") (pinfunction "PA7_(AD7)_71") (pintype "bidirectional"))
      (node (ref "T4") (pin "C") (pinfunction "C_C") (pintype "passive"))
    )
    (net (code "9") (name "C0") (class "Default")
      (node (ref "IC1") (pin "53") (pinfunction "PC0_(A8)_53") (pintype "bidirectional"))
      (node (ref "T12") (pin "C") (pinfunction "C_C") (pintype "passive"))
    )
    (net (code "10") (name "C1") (class "Default")
      (node (ref "IC1") (pin "54") (pinfunction "PC1_(A9)_54") (pintype "bidirectional"))
      (node (ref "T11") (pin "C") (pinfunction "C_C") (pintype "passive"))
    )
    (net (code "11") (name "C2") (class "Default")
      (node (ref "IC1") (pin "55") (pinfunction "PC2_(A10)_55") (pintype "bidirectional"))
      (node (ref "T10") (pin "C") (pinfunction "C_C") (pintype "passive"))
    )
    (net (code "12") (name "C3") (class "Default")
      (node (ref "IC1") (pin "56") (pinfunction "PC3_(A11)_56") (pintype "bidirectional"))
      (node (ref "T9") (pin "C") (pinfunction "C_C") (pintype "passive"))
    )
    (net (code "13") (name "C4") (class "Default")
      (node (ref "IC1") (pin "57") (pinfunction "PC4_(A12)_57") (pintype "bidirectional"))
      (node (ref "OK3") (pin "10") (pinfunction "COL_10") (pintype "passive"))
    )
    (net (code "14") (name "C5") (class "Default")
      (node (ref "IC1") (pin "58") (pinfunction "PC5_(A13)_58") (pintype "bidirectional"))
      (node (ref "OK3") (pin "12") (pinfunction "COL_12") (pintype "passive"))
    )
    (net (code "15") (name "C6") (class "Default")
      (node (ref "IC1") (pin "59") (pinfunction "PC6_(A14)_59") (pintype "bidirectional"))
      (node (ref "OK3") (pin "14") (pinfunction "COL_14") (pintype "passive"))
    )
    (net (code "16") (name "C7") (class "Default")
      (node (ref "IC1") (pin "60") (pinfunction "PC7_(A15)_60") (pintype "bidirectional"))
      (node (ref "OK3") (pin "16") (pinfunction "COL_16") (pintype "passive"))
    )
    (net (code "17") (name "CAN_H") (class "Default")
      (node (ref "IC2") (pin "7") (pinfunction "CANH_7") (pintype "bidirectional"))
      (node (ref "J1") (pin "8") (pinfunction "8_8") (pintype "passive"))
      (node (ref "J2") (pin "8") (pinfunction "8_8") (pintype "passive"))
      (node (ref "TERM") (pin "2") (pinfunction "2_2") (pintype "passive"))
      (node (ref "X17") (pin "2") (pinfunction "2_2") (pintype "passive"))
    )
    (net (code "18") (name "CAN_L") (class "Default")
      (node (ref "IC2") (pin "6") (pinfunction "CANL_6") (pintype "bidirectional"))
      (node (ref "J1") (pin "7") (pinfunction "7_7") (pintype "passive"))
      (node (ref "J2") (pin "7") (pinfunction "7_7") (pintype "passive"))
      (node (ref "R3") (pin "1") (pinfunction "1_1") (pintype "passive"))
      (node (ref "X17") (pin "3") (pinfunction "3_3") (pintype "passive"))
    )
    (net (code "19") (name "CAN_V+") (class "Default")
      (node (ref "C9") (pin "+") (pinfunction "+_+") (pintype "passive"))
      (node (ref "IC8") (pin "1") (pinfunction "VI_1") (pintype "input"))
      (node (ref "J1") (pin "5") (pinfunction "5_5") (pintype "passive"))
      (node (ref "J1") (pin "6") (pinfunction "6_6") (pintype "passive"))
      (node (ref "J2") (pin "5") (pinfunction "5_5") (pintype "passive"))
      (node (ref "J2") (pin "6") (pinfunction "6_6") (pintype "passive"))
      (node (ref "X5") (pin "2") (pinfunction "2_2") (pintype "passive"))
      (node (ref "X7") (pin "2") (pinfunction "2_2") (pintype "passive"))
    )
    (net (code "20") (name "CS") (class "Default")
      (node (ref "IC1") (pin "19") (pinfunction "(~{SS/PCINT0})_PB0_19") (pintype "bidirectional"))
      (node (ref "IC3") (pin "16") (pinfunction "~{CS}_16") (pintype "input"))
    )
    (net (code "21") (name "D+") (class "Default")
      (node (ref "IC4") (pin "29") (pinfunction "D+_29") (pintype "bidirectional"))
      (node (ref "R43") (pin "1") (pinfunction "1_1") (pintype "passive"))
    )
    (net (code "22") (name "D-") (class "Default")
      (node (ref "IC4") (pin "30") (pinfunction "D-_30") (pintype "bidirectional"))
      (node (ref "R42") (pin "1") (pinfunction "1_1") (pintype "passive"))
    )
    (net (code "23") (name "DCC1") (class "Default")
      (node (ref "B1") (pin "AC2") (pinfunction "AC2_AC2") (pintype "passive"))
      (node (ref "B2") (pin "AC2") (pinfunction "AC2_AC2") (pintype "passive"))
      (node (ref "B3") (pin "AC2") (pinfunction "AC2_AC2") (pintype "passive"))
      (node (ref "B4") (pin "AC2") (pinfunction "AC2_AC2") (pintype "passive"))
      (node (ref "C11") (pin "2") (pinfunction "2_2") (pintype "passive"))
      (node (ref "C12") (pin "2") (pinfunction "2_2") (pintype "passive"))
      (node (ref "C13") (pin "2") (pinfunction "2_2") (pintype "passive"))
      (node (ref "C14") (pin "2") (pinfunction "2_2") (pintype "passive"))
      (node (ref "OK1") (pin "2") (pinfunction "C_2") (pintype "passive"))
      (node (ref "OK1") (pin "4") (pinfunction "C_4") (pintype "passive"))
      (node (ref "OK1") (pin "6") (pinfunction "C_6") (pintype "passive"))
      (node (ref "OK1") (pin "8") (pinfunction "C_8") (pintype "passive"))
      (node (ref "X1") (pin "1") (pinfunction "1_1") (pintype "passive"))
    )
    (net (code "24") (name "DCC2") (class "Default")
      (node (ref "B5") (pin "AC2") (pinfunction "AC2_AC2") (pintype "passive"))
      (node (ref "B6") (pin "AC2") (pinfunction "AC2_AC2") (pintype "passive"))
      (node (ref "B7") (pin "AC2") (pinfunction "AC2_AC2") (pintype "passive"))
      (node (ref "B8") (pin "AC2") (pinfunction "AC2_AC2") (pintype "passive"))
      (node (ref "C15") (pin "2") (pinfunction "2_2") (pintype "passive"))
      (node (ref "C16") (pin "2") (pinfunction "2_2") (pintype "passive"))
      (node (ref "C17") (pin "2") (pinfunction "2_2") (pintype "passive"))
      (node (ref "C18") (pin "2") (pinfunction "2_2") (pintype "passive"))
      (node (ref "OK2") (pin "2") (pinfunction "C_2") (pintype "passive"))
      (node (ref "OK2") (pin "4") (pinfunction "C_4") (pintype "passive"))
      (node (ref "OK2") (pin "6") (pinfunction "C_6") (pintype "passive"))
      (node (ref "OK2") (pin "8") (pinfunction "C_8") (pintype "passive"))
      (node (ref "X1") (pin "10") (pinfunction "10_10") (pintype "passive"))
    )
    (net (code "25") (name "DCC3") (class "Default")
      (node (ref "B10") (pin "AC2") (pinfunction "AC2_AC2") (pintype "passive"))
      (node (ref "B11") (pin "AC2") (pinfunction "AC2_AC2") (pintype "passive"))
      (node (ref "B12") (pin "AC2") (pinfunction "AC2_AC2") (pintype "passive"))
      (node (ref "B9") (pin "AC2") (pinfunction "AC2_AC2") (pintype "passive"))
      (node (ref "C19") (pin "2") (pinfunction "2_2") (pintype "passive"))
      (node (ref "C20") (pin "2") (pinfunction "2_2") (pintype "passive"))
      (node (ref "C21") (pin "2") (pinfunction "2_2") (pintype "passive"))
      (node (ref "C22") (pin "2") (pinfunction "2_2") (pintype "passive"))
      (node (ref "OK3") (pin "2") (pinfunction "C_2") (pintype "passive"))
      (node (ref "OK3") (pin "4") (pinfunction "C_4") (pintype "passive"))
      (node (ref "OK3") (pin "6") (pinfunction "C_6") (pintype "passive"))
      (node (ref "OK3") (pin "8") (pinfunction "C_8") (pintype "passive"))
      (node (ref "X2") (pin "1") (pinfunction "1_1") (pintype "passive"))
    )
    (net (code "26") (name "DCC4") (class "Default")
      (node (ref "B13") (pin "AC2") (pinfunction "AC2_AC2") (pintype "passive"))
      (node (ref "B14") (pin "AC2") (pinfunction "AC2_AC2") (pintype "passive"))
      (node (ref "B15") (pin "AC2") (pinfunction "AC2_AC2") (pintype "passive"))
      (node (ref "B16") (pin "AC2") (pinfunction "AC2_AC2") (pintype "passive"))
      (node (ref "C23") (pin "2") (pinfunction "2_2") (pintype "passive"))
      (node (ref "C24") (pin "2") (pinfunction "2_2") (pintype "passive"))
      (node (ref "C25") (pin "2") (pinfunction "2_2") (pintype "passive"))
      (node (ref "C26") (pin "2") (pinfunction "2_2") (pintype "passive"))
      (node (ref "OK4") (pin "2") (pinfunction "C_2") (pintype "passive"))
      (node (ref "OK4") (pin "4") (pinfunction "C_4") (pintype "passive"))
      (node (ref "OK4") (pin "6") (pinfunction "C_6") (pintype "passive"))
      (node (ref "OK4") (pin "8") (pinfunction "C_8") (pintype "passive"))
      (node (ref "X2") (pin "10") (pinfunction "10_10") (pintype "passive"))
    )
    (net (code "27") (name "DCC5") (class "Default")
      (node (ref "B17") (pin "AC2") (pinfunction "AC2_AC2") (pintype "passive"))
      (node (ref "B18") (pin "AC2") (pinfunction "AC2_AC2") (pintype "passive"))
      (node (ref "B19") (pin "AC2") (pinfunction "AC2_AC2") (pintype "passive"))
      (node (ref "B20") (pin "AC2") (pinfunction "AC2_AC2") (pintype "passive"))
      (node (ref "C27") (pin "2") (pinfunction "2_2") (pintype "passive"))
      (node (ref "C28") (pin "2") (pinfunction "2_2") (pintype "passive"))
      (node (ref "C29") (pin "2") (pinfunction "2_2") (pintype "passive"))
      (node (ref "C30") (pin "2") (pinfunction "2_2") (pintype "passive"))
      (node (ref "OK5") (pin "2") (pinfunction "C_2") (pintype "passive"))
      (node (ref "OK5") (pin "4") (pinfunction "C_4") (pintype "passive"))
      (node (ref "OK5") (pin "6") (pinfunction "C_6") (pintype "passive"))
      (node (ref "OK5") (pin "8") (pinfunction "C_8") (pintype "passive"))
      (node (ref "X3") (pin "1") (pinfunction "1_1") (pintype "passive"))
    )
    (net (code "28") (name "DCC6") (class "Default")
      (node (ref "B21") (pin "AC2") (pinfunction "AC2_AC2") (pintype "passive"))
      (node (ref "B22") (pin "AC2") (pinfunction "AC2_AC2") (pintype "passive"))
      (node (ref "B23") (pin "AC2") (pinfunction "AC2_AC2") (pintype "passive"))
      (node (ref "B24") (pin "AC2") (pinfunction "AC2_AC2") (pintype "passive"))
      (node (ref "C31") (pin "2") (pinfunction "2_2") (pintype "passive"))
      (node (ref "C32") (pin "2") (pinfunction "2_2") (pintype "passive"))
      (node (ref "C33") (pin "2") (pinfunction "2_2") (pintype "passive"))
      (node (ref "C34") (pin "2") (pinfunction "2_2") (pintype "passive"))
      (node (ref "OK6") (pin "2") (pinfunction "C_2") (pintype "passive"))
      (node (ref "OK6") (pin "4") (pinfunction "C_4") (pintype "passive"))
      (node (ref "OK6") (pin "6") (pinfunction "C_6") (pintype "passive"))
      (node (ref "OK6") (pin "8") (pinfunction "C_8") (pintype "passive"))
      (node (ref "X3") (pin "10") (pinfunction "10_10") (pintype "passive"))
    )
    (net (code "29") (name "DCC7") (class "Default")
      (node (ref "B25") (pin "AC2") (pinfunction "AC2_AC2") (pintype "passive"))
      (node (ref "B26") (pin "AC2") (pinfunction "AC2_AC2") (pintype "passive"))
      (node (ref "B27") (pin "AC2") (pinfunction "AC2_AC2") (pintype "passive"))
      (node (ref "B28") (pin "AC2") (pinfunction "AC2_AC2") (pintype "passive"))
      (node (ref "C35") (pin "2") (pinfunction "2_2") (pintype "passive"))
      (node (ref "C36") (pin "2") (pinfunction "2_2") (pintype "passive"))
      (node (ref "C37") (pin "2") (pinfunction "2_2") (pintype "passive"))
      (node (ref "C38") (pin "2") (pinfunction "2_2") (pintype "passive"))
      (node (ref "OK7") (pin "2") (pinfunction "C_2") (pintype "passive"))
      (node (ref "OK7") (pin "4") (pinfunction "C_4") (pintype "passive"))
      (node (ref "OK7") (pin "6") (pinfunction "C_6") (pintype "passive"))
      (node (ref "OK7") (pin "8") (pinfunction "C_8") (pintype "passive"))
      (node (ref "X4") (pin "1") (pinfunction "1_1") (pintype "passive"))
    )
    (net (code "30") (name "DCC8") (class "Default")
      (node (ref "B29") (pin "AC2") (pinfunction "AC2_AC2") (pintype "passive"))
      (node (ref "B30") (pin "AC2") (pinfunction "AC2_AC2") (pintype "passive"))
      (node (ref "B31") (pin "AC2") (pinfunction "AC2_AC2") (pintype "passive"))
      (node (ref "B32") (pin "AC2") (pinfunction "AC2_AC2") (pintype "passive"))
      (node (ref "C39") (pin "2") (pinfunction "2_2") (pintype "passive"))
      (node (ref "C40") (pin "2") (pinfunction "2_2") (pintype "passive"))
      (node (ref "C41") (pin "2") (pinfunction "2_2") (pintype "passive"))
      (node (ref "C42") (pin "2") (pinfunction "2_2") (pintype "passive"))
      (node (ref "OK8") (pin "2") (pinfunction "C_2") (pintype "passive"))
      (node (ref "OK8") (pin "4") (pinfunction "C_4") (pintype "passive"))
      (node (ref "OK8") (pin "6") (pinfunction "C_6") (pintype "passive"))
      (node (ref "OK8") (pin "8") (pinfunction "C_8") (pintype "passive"))
      (node (ref "X4") (pin "10") (pinfunction "10_10") (pintype "passive"))
    )
    (net (code "31") (name "DTR") (class "Default")
      (node (ref "IC4") (pin "13") (pinfunction "PD7_13") (pintype "bidirectional"))
      (node (ref "R46") (pin "2") (pinfunction "2_2") (pintype "passive"))
    )
    (net (code "32") (name "E0") (class "Default")
      (node (ref "IC1") (pin "26") (pinfunction "(OC0A/OC1C/PCINT7)_PB7_26") (pintype "bidirectional"))
      (node (ref "T24") (pin "C") (pinfunction "C_C") (pintype "passive"))
    )
    (net (code "33") (name "E1") (class "Default")
      (node (ref "IC1") (pin "25") (pinfunction "(OC1B/PCINT6)_PB6_25") (pintype "bidirectional"))
      (node (ref "T23") (pin "C") (pinfunction "C_C") (pintype "passive"))
    )
    (net (code "34") (name "E2") (class "Default")
      (node (ref "IC1") (pin "4") (pinfunction "(XCK0/AIN0)_PE2_4") (pintype "bidirectional"))
      (node (ref "T22") (pin "C") (pinfunction "C_C") (pintype "passive"))
    )
    (net (code "35") (name "E3") (class "Default")
      (node (ref "IC1") (pin "5") (pinfunction "(OC3A/AIN1)_PE3_5") (pintype "bidirectional"))
      (node (ref "T21") (pin "C") (pinfunction "C_C") (pintype "passive"))
    )
    (net (code "36") (name "E4") (class "Default")
      (node (ref "IC1") (pin "6") (pinfunction "(OC3B/INT4)_PE4_6") (pintype "bidirectional"))
      (node (ref "OK6") (pin "10") (pinfunction "COL_10") (pintype "passive"))
    )
    (net (code "37") (name "E5") (class "Default")
      (node (ref "IC1") (pin "7") (pinfunction "(OC3C/INT5)_PE5_7") (pintype "bidirectional"))
      (node (ref "OK6") (pin "12") (pinfunction "COL_12") (pintype "passive"))
    )
    (net (code "38") (name "E6") (class "Default")
      (node (ref "IC1") (pin "8") (pinfunction "(T3/INT6)_PE6_8") (pintype "bidirectional"))
      (node (ref "OK6") (pin "14") (pinfunction "COL_14") (pintype "passive"))
    )
    (net (code "39") (name "E7") (class "Default")
      (node (ref "IC1") (pin "9") (pinfunction "(CLKO/ICP3/INT7)_PE7_9") (pintype "bidirectional"))
      (node (ref "OK6") (pin "16") (pinfunction "COL_16") (pintype "passive"))
    )
    (net (code "40") (name "F0") (class "Default")
      (node (ref "IC1") (pin "97") (pinfunction "PF0_(ADC0)_97") (pintype "bidirectional"))
      (node (ref "T25") (pin "C") (pinfunction "C_C") (pintype "passive"))
    )
    (net (code "41") (name "F1") (class "Default")
      (node (ref "IC1") (pin "96") (pinfunction "PF1_(ADC1)_96") (pintype "bidirectional"))
      (node (ref "T26") (pin "C") (pinfunction "C_C") (pintype "passive"))
    )
    (net (code "42") (name "F2") (class "Default")
      (node (ref "IC1") (pin "95") (pinfunction "PF2_(ADC2)_95") (pintype "bidirectional"))
      (node (ref "T27") (pin "C") (pinfunction "C_C") (pintype "passive"))
    )
    (net (code "43") (name "F3") (class "Default")
      (node (ref "IC1") (pin "94") (pinfunction "PF3_(ADC3)_94") (pintype "bidirectional"))
      (node (ref "T28") (pin "C") (pinfunction "C_C") (pintype "passive"))
    )
    (net (code "44") (name "F4") (class "Default")
      (node (ref "IC1") (pin "93") (pinfunction "PF4_(ADC4/TCK)_93") (pintype "bidirectional"))
      (node (ref "OK7") (pin "16") (pinfunction "COL_16") (pintype "passive"))
    )
    (net (code "45") (name "F5") (class "Default")
      (node (ref "IC1") (pin "92") (pinfunction "PF5_(ADC5/TMS)_92") (pintype "bidirectional"))
      (node (ref "OK7") (pin "14") (pinfunction "COL_14") (pintype "passive"))
    )
    (net (code "46") (name "F6") (class "Default")
      (node (ref "IC1") (pin "91") (pinfunction "PF6_(ADC6/TDO)_91") (pintype "bidirectional"))
      (node (ref "OK7") (pin "12") (pinfunction "COL_12") (pintype "passive"))
    )
    (net (code "47") (name "F7") (class "Default")
      (node (ref "IC1") (pin "90") (pinfunction "PF7_(ADC7/TDI)_90") (pintype "bidirectional"))
      (node (ref "OK7") (pin "10") (pinfunction "COL_10") (pintype "passive"))
    )
    (net (code "48") (name "GND") (class "Default")
      (node (ref "C1") (pin "2") (pinfunction "2_2") (pintype "passive"))
      (node (ref "C10") (pin "2") (pinfunction "2_2") (pintype "passive"))
      (node (ref "C2") (pin "2") (pinfunction "2_2") (pintype "passive"))
      (node (ref "C3") (pin "2") (pinfunction "2_2") (pintype "passive"))
      (node (ref "C4") (pin "2") (pinfunction "2_2") (pintype "passive"))
      (node (ref "C5") (pin "2") (pinfunction "2_2") (pintype "passive"))
      (node (ref "C6") (pin "2") (pinfunction "2_2") (pintype "passive"))
      (node (ref "C7") (pin "2") (pinfunction "2_2") (pintype "passive"))
      (node (ref "C8") (pin "2") (pinfunction "2_2") (pintype "passive"))
      (node (ref "C9") (pin "-") (pinfunction "-_-") (pintype "passive"))
      (node (ref "IC1") (pin "11") (pinfunction "GND_2_11") (pintype "passive"))
      (node (ref "IC1") (pin "32") (pinfunction "GND_4_32") (pintype "passive"))
      (node (ref "IC1") (pin "62") (pinfunction "GND_3_62") (pintype "passive"))
      (node (ref "IC1") (pin "81") (pinfunction "GND_5_81") (pintype "passive"))
      (node (ref "IC1") (pin "99") (pinfunction "GND_99") (pintype "passive"))
      (node (ref "IC2") (pin "2") (pinfunction "VSS_2") (pintype "passive"))
      (node (ref "IC2") (pin "8") (pinfunction "RS_8") (pintype "input"))
      (node (ref "IC3") (pin "9") (pinfunction "VSS_9") (pintype "power_in"))
      (node (ref "IC5") (pin "4") (pinfunction "GND1_4") (pintype "passive"))
      (node (ref "IC8") (pin "3") (pinfunction "GND_3") (pintype "passive"))
      (node (ref "ISP") (pin "6") (pinfunction "S_6") (pintype "passive"))
      (node (ref "I²C") (pin "3") (pinfunction "S_3") (pintype "passive"))
      (node (ref "J1") (pin "3") (pinfunction "3_3") (pintype "passive"))
      (node (ref "J1") (pin "4") (pinfunction "4_4") (pintype "passive"))
      (node (ref "J1") (pin "SHELL") (pinfunction "SHIELD_SHELL") (pintype "passive"))
      (node (ref "J1") (pin "SHELL1") (pinfunction "SHIELD_SHELL1") (pintype "passive"))
      (node (ref "J2") (pin "3") (pinfunction "3_3") (pintype "passive"))
      (node (ref "J2") (pin "4") (pinfunction "4_4") (pintype "passive"))
      (node (ref "J2") (pin "SHELL") (pinfunction "SHIELD_SHELL") (pintype "passive"))
      (node (ref "J2") (pin "SHELL1") (pinfunction "SHIELD_SHELL1") (pintype "passive"))
      (node (ref "OK1") (pin "11") (pinfunction "EMIT_11") (pintype "passive"))
      (node (ref "OK1") (pin "13") (pinfunction "EMIT_13") (pintype "passive"))
      (node (ref "OK1") (pin "15") (pinfunction "EMIT_15") (pintype "passive"))
      (node (ref "OK1") (pin "9") (pinfunction "EMIT_9") (pintype "passive"))
      (node (ref "OK2") (pin "11") (pinfunction "EMIT_11") (pintype "passive"))
      (node (ref "OK2") (pin "13") (pinfunction "EMIT_13") (pintype "passive"))
      (node (ref "OK2") (pin "15") (pinfunction "EMIT_15") (pintype "passive"))
      (node (ref "OK2") (pin "9") (pinfunction "EMIT_9") (pintype "passive"))
      (node (ref "OK3") (pin "11") (pinfunction "EMIT_11") (pintype "passive"))
      (node (ref "OK3") (pin "13") (pinfunction "EMIT_13") (pintype "passive"))
      (node (ref "OK3") (pin "15") (pinfunction "EMIT_15") (pintype "passive"))
      (node (ref "OK3") (pin "9") (pinfunction "EMIT_9") (pintype "passive"))
      (node (ref "OK4") (pin "11") (pinfunction "EMIT_11") (pintype "passive"))
      (node (ref "OK4") (pin "13") (pinfunction "EMIT_13") (pintype "passive"))
      (node (ref "OK4") (pin "15") (pinfunction "EMIT_15") (pintype "passive"))
      (node (ref "OK4") (pin "9") (pinfunction "EMIT_9") (pintype "passive"))
      (node (ref "OK5") (pin "11") (pinfunction "EMIT_11") (pintype "passive"))
      (node (ref "OK5") (pin "13") (pinfunction "EMIT_13") (pintype "passive"))
      (node (ref "OK5") (pin "15") (pinfunction "EMIT_15") (pintype "passive"))
      (node (ref "OK5") (pin "9") (pinfunction "EMIT_9") (pintype "passive"))
      (node (ref "OK6") (pin "11") (pinfunction "EMIT_11") (pintype "passive"))
      (node (ref "OK6") (pin "13") (pinfunction "EMIT_13") (pintype "passive"))
      (node (ref "OK6") (pin "15") (pinfunction "EMIT_15") (pintype "passive"))
      (node (ref "OK6") (pin "9") (pinfunction "EMIT_9") (pintype "passive"))
      (node (ref "OK7") (pin "11") (pinfunction "EMIT_11") (pintype "passive"))
      (node (ref "OK7") (pin "13") (pinfunction "EMIT_13") (pintype "passive"))
      (node (ref "OK7") (pin "15") (pinfunction "EMIT_15") (pintype "passive"))
      (node (ref "OK7") (pin "9") (pinfunction "EMIT_9") (pintype "passive"))
      (node (ref "OK8") (pin "11") (pinfunction "EMIT_11") (pintype "passive"))
      (node (ref "OK8") (pin "13") (pinfunction "EMIT_13") (pintype "passive"))
      (node (ref "OK8") (pin "15") (pinfunction "EMIT_15") (pintype "passive"))
      (node (ref "OK8") (pin "9") (pinfunction "EMIT_9") (pintype "passive"))
      (node (ref "OK9") (pin "3") (pinfunction "EMIT_3") (pintype "passive"))
      (node (ref "R4") (pin "2") (pinfunction "2_2") (pintype "passive"))
      (node (ref "R5") (pin "2") (pinfunction "2_2") (pintype "passive"))
      (node (ref "S1") (pin "1") (pinfunction "1_1") (pintype "passive"))
      (node (ref "S1") (pin "2") (pinfunction "2_2") (pintype "passive"))
      (node (ref "S1") (pin "3") (pinfunction "3_3") (pintype "passive"))
      (node (ref "S1") (pin "4") (pinfunction "4_4") (pintype "passive"))
      (node (ref "U$15") (pin "P$1") (pinfunction "P$1_P$1") (pintype "bidirectional"))
      (node (ref "U$15") (pin "P$2") (pinfunction "P$2_P$2") (pintype "bidirectional"))
      (node (ref "X17") (pin "1") (pinfunction "1_1") (pintype "passive"))
      (node (ref "X5") (pin "1") (pinfunction "1_1") (pintype "passive"))
      (node (ref "X7") (pin "1") (pinfunction "1_1") (pintype "passive"))
    )
    (net (code "49") (name "GND2") (class "Default")
      (node (ref "C43") (pin "2") (pinfunction "2_2") (pintype "passive"))
      (node (ref "C44") (pin "2") (pinfunction "2_2") (pintype "passive"))
      (node (ref "C45") (pin "2") (pinfunction "2_2") (pintype "passive"))
      (node (ref "C47") (pin "2") (pinfunction "2_2") (pintype "passive"))
      (node (ref "GND") (pin "TP") (pinfunction "TP_TP") (pintype "input"))
      (node (ref "IC4") (pin "28") (pinfunction "UGND_28") (pintype "power_in"))
      (node (ref "IC4") (pin "3") (pinfunction "GND_3") (pintype "power_in"))
      (node (ref "IC4") (pin "33") (pinfunction "EXP_33") (pintype "power_in"))
      (node (ref "IC5") (pin "5") (pinfunction "GND2_5") (pintype "passive"))
      (node (ref "X6") (pin "5") (pinfunction "5_5") (pintype "passive"))
    )
    (net (code "50") (name "H0") (class "Default")
      (node (ref "IC1") (pin "12") (pinfunction "(RXD2)_PH0_12") (pintype "bidirectional"))
      (node (ref "T20") (pin "C") (pinfunction "C_C") (pintype "passive"))
    )
    (net (code "51") (name "H1") (class "Default")
      (node (ref "IC1") (pin "13") (pinfunction "(TXD2)_PH1_13") (pintype "bidirectional"))
      (node (ref "T19") (pin "C") (pinfunction "C_C") (pintype "passive"))
    )
    (net (code "52") (name "H2") (class "Default")
      (node (ref "IC1") (pin "14") (pinfunction "(XCK2)_PH2_14") (pintype "bidirectional"))
      (node (ref "T18") (pin "C") (pinfunction "C_C") (pintype "passive"))
    )
    (net (code "53") (name "H3") (class "Default")
      (node (ref "IC1") (pin "15") (pinfunction "(OC4A)_PH3_15") (pintype "bidirectional"))
      (node (ref "T17") (pin "C") (pinfunction "C_C") (pintype "passive"))
    )
    (net (code "54") (name "H4") (class "Default")
      (node (ref "IC1") (pin "16") (pinfunction "(OC4B)_PH4_16") (pintype "bidirectional"))
      (node (ref "OK5") (pin "16") (pinfunction "COL_16") (pintype "passive"))
    )
    (net (code "55") (name "H5") (class "Default")
      (node (ref "IC1") (pin "17") (pinfunction "(OC4C)_PH5_17") (pintype "bidirectional"))
      (node (ref "OK5") (pin "14") (pinfunction "COL_14") (pintype "passive"))
    )
    (net (code "56") (name "H6") (class "Default")
      (node (ref "IC1") (pin "18") (pinfunction "(OC2B)_PH6_18") (pintype "bidirectional"))
      (node (ref "OK5") (pin "12") (pinfunction "COL_12") (pintype "passive"))
    )
    (net (code "57") (name "H7") (class "Default")
      (node (ref "IC1") (pin "27") (pinfunction "(T4)_PH7_27") (pintype "bidirectional"))
      (node (ref "OK5") (pin "10") (pinfunction "COL_10") (pintype "passive"))
    )
    (net (code "58") (name "INT") (class "Default")
      (node (ref "IC1") (pin "45") (pinfunction "(RXD1/INT2)_PD2_45") (pintype "bidirectional"))
      (node (ref "IC3") (pin "12") (pinfunction "~{INT}_12") (pintype "output"))
    )
    (net (code "59") (name "J0") (class "Default")
      (node (ref "IC1") (pin "63") (pinfunction "PJ0_(RXD3/PCINT9)_63") (pintype "bidirectional"))
      (node (ref "T8") (pin "C") (pinfunction "C_C") (pintype "passive"))
    )
    (net (code "60") (name "J1") (class "Default")
      (node (ref "IC1") (pin "64") (pinfunction "PJ1_(TXD3/PCINT10)_64") (pintype "bidirectional"))
      (node (ref "T7") (pin "C") (pinfunction "C_C") (pintype "passive"))
    )
    (net (code "61") (name "J2") (class "Default")
      (node (ref "IC1") (pin "65") (pinfunction "PJ2_(XCK3/PCINT11)_65") (pintype "bidirectional"))
      (node (ref "T6") (pin "C") (pinfunction "C_C") (pintype "passive"))
    )
    (net (code "62") (name "J3") (class "Default")
      (node (ref "IC1") (pin "66") (pinfunction "PJ3_(PCINT12)_66") (pintype "bidirectional"))
      (node (ref "T5") (pin "C") (pinfunction "C_C") (pintype "passive"))
    )
    (net (code "63") (name "J4") (class "Default")
      (node (ref "IC1") (pin "67") (pinfunction "PJ4_(PCINT13)_67") (pintype "bidirectional"))
      (node (ref "OK2") (pin "10") (pinfunction "COL_10") (pintype "passive"))
    )
    (net (code "64") (name "J5") (class "Default")
      (node (ref "IC1") (pin "68") (pinfunction "PJ5_(PCINT14)_68") (pintype "bidirectional"))
      (node (ref "OK2") (pin "12") (pinfunction "COL_12") (pintype "passive"))
    )
    (net (code "65") (name "J6") (class "Default")
      (node (ref "IC1") (pin "69") (pinfunction "PJ6_(PCINT15)_69") (pintype "bidirectional"))
      (node (ref "OK2") (pin "14") (pinfunction "COL_14") (pintype "passive"))
    )
    (net (code "66") (name "J7") (class "Default")
      (node (ref "IC1") (pin "79") (pinfunction "PJ7_79") (pintype "bidirectional"))
      (node (ref "OK2") (pin "16") (pinfunction "COL_16") (pintype "passive"))
    )
    (net (code "67") (name "K0") (class "Default")
      (node (ref "IC1") (pin "89") (pinfunction "PK0_(ADC8/PCINT16)_89") (pintype "bidirectional"))
      (node (ref "T29") (pin "C") (pinfunction "C_C") (pintype "passive"))
    )
    (net (code "68") (name "K1") (class "Default")
      (node (ref "IC1") (pin "88") (pinfunction "PK1_(ADC9/PCINT17)_88") (pintype "bidirectional"))
      (node (ref "T30") (pin "C") (pinfunction "C_C") (pintype "passive"))
    )
    (net (code "69") (name "K2") (class "Default")
      (node (ref "IC1") (pin "87") (pinfunction "PK2_(ADC10/PCINT18)_87") (pintype "bidirectional"))
      (node (ref "T31") (pin "C") (pinfunction "C_C") (pintype "passive"))
    )
    (net (code "70") (name "K3") (class "Default")
      (node (ref "IC1") (pin "86") (pinfunction "PK3_(ADC11/PCINT19)_86") (pintype "bidirectional"))
      (node (ref "T32") (pin "C") (pinfunction "C_C") (pintype "passive"))
    )
    (net (code "71") (name "K4") (class "Default")
      (node (ref "IC1") (pin "85") (pinfunction "PK4_(ADC12/PCINT20)_85") (pintype "bidirectional"))
      (node (ref "OK8") (pin "10") (pinfunction "COL_10") (pintype "passive"))
    )
    (net (code "72") (name "K5") (class "Default")
      (node (ref "IC1") (pin "84") (pinfunction "PK5_(ADC13/PCINT21)_84") (pintype "bidirectional"))
      (node (ref "OK8") (pin "12") (pinfunction "COL_12") (pintype "passive"))
    )
    (net (code "73") (name "K6") (class "Default")
      (node (ref "IC1") (pin "83") (pinfunction "PK6_(ADC14/PCINT22)_83") (pintype "bidirectional"))
      (node (ref "OK8") (pin "14") (pinfunction "COL_14") (pintype "passive"))
    )
    (net (code "74") (name "K7") (class "Default")
      (node (ref "IC1") (pin "82") (pinfunction "PK7_(ADC15/PCINT23)_82") (pintype "bidirectional"))
      (node (ref "OK8") (pin "16") (pinfunction "COL_16") (pintype "passive"))
    )
    (net (code "75") (name "L0") (class "Default")
      (node (ref "IC1") (pin "35") (pinfunction "(ICP4)_PL0_35") (pintype "bidirectional"))
      (node (ref "OK4") (pin "16") (pinfunction "COL_16") (pintype "passive"))
    )
    (net (code "76") (name "L1") (class "Default")
      (node (ref "IC1") (pin "36") (pinfunction "(ICP5)_PL1_36") (pintype "bidirectional"))
      (node (ref "OK4") (pin "14") (pinfunction "COL_14") (pintype "passive"))
    )
    (net (code "77") (name "L2") (class "Default")
      (node (ref "IC1") (pin "37") (pinfunction "(T5)_PL2_37") (pintype "bidirectional"))
      (node (ref "OK4") (pin "12") (pinfunction "COL_12") (pintype "passive"))
    )
    (net (code "78") (name "L3") (class "Default")
      (node (ref "IC1") (pin "38") (pinfunction "(OC5A)_PL3_38") (pintype "bidirectional"))
      (node (ref "OK4") (pin "10") (pinfunction "COL_10") (pintype "passive"))
    )
    (net (code "79") (name "L4") (class "Default")
      (node (ref "IC1") (pin "39") (pinfunction "(OC5B)_PL4_39") (pintype "bidirectional"))
      (node (ref "T16") (pin "C") (pinfunction "C_C") (pintype "passive"))
    )
    (net (code "80") (name "L5") (class "Default")
      (node (ref "IC1") (pin "40") (pinfunction "OC5C)_PL5_40") (pintype "bidirectional"))
      (node (ref "T15") (pin "C") (pinfunction "C_C") (pintype "passive"))
    )
    (net (code "81") (name "L6") (class "Default")
      (node (ref "IC1") (pin "41") (pinfunction "PL6_41") (pintype "bidirectional"))
      (node (ref "T14") (pin "C") (pinfunction "C_C") (pintype "passive"))
    )
    (net (code "82") (name "L7") (class "Default")
      (node (ref "IC1") (pin "42") (pinfunction "PL7_42") (pintype "bidirectional"))
      (node (ref "T13") (pin "C") (pinfunction "C_C") (pintype "passive"))
    )
    (net (code "83") (name "MISO") (class "Default")
      (node (ref "IC1") (pin "22") (pinfunction "(MISO/PCINT3)_PB3_22") (pintype "bidirectional"))
      (node (ref "IC3") (pin "15") (pinfunction "SO_15") (pintype "output"))
      (node (ref "ISP") (pin "1") (pinfunction "S_1") (pintype "passive"))
    )
    (net (code "84") (name "MISO2") (class "Default")
      (node (ref "IC4") (pin "17") (pinfunction "PB3_17") (pintype "bidirectional"))
      (node (ref "MISO") (pin "TP") (pinfunction "TP_TP") (pintype "input"))
    )
    (net (code "85") (name "MOSI") (class "Default")
      (node (ref "IC1") (pin "21") (pinfunction "(MOSI/PCINT2)_PB2_21") (pintype "bidirectional"))
      (node (ref "IC3") (pin "14") (pinfunction "SI_14") (pintype "input"))
      (node (ref "ISP") (pin "4") (pinfunction "S_4") (pintype "passive"))
    )
    (net (code "86") (name "MOSI2") (class "Default")
      (node (ref "IC4") (pin "16") (pinfunction "PB2_16") (pintype "bidirectional"))
      (node (ref "MOSI") (pin "TP") (pinfunction "TP_TP") (pintype "input"))
    )
    (net (code "87") (name "Net-(B1-Pad+)") (class "Default")
      (node (ref "B1") (pin "+") (pinfunction "+_+") (pintype "passive"))
      (node (ref "B1") (pin "-") (pinfunction "-_-") (pintype "passive"))
    )
    (net (code "88") (name "Net-(B1-PadAC1)") (class "Default")
      (node (ref "B1") (pin "AC1") (pinfunction "AC1_AC1") (pintype "passive"))
      (node (ref "R9") (pin "2") (pinfunction "2_2") (pintype "passive"))
      (node (ref "X1") (pin "2") (pinfunction "2_2") (pintype "passive"))
    )
    (net (code "89") (name "Net-(B2-Pad+)") (class "Default")
      (node (ref "B2") (pin "+") (pinfunction "+_+") (pintype "passive"))
      (node (ref "B2") (pin "-") (pinfunction "-_-") (pintype "passive"))
    )
    (net (code "90") (name "Net-(B2-PadAC1)") (class "Default")
      (node (ref "B2") (pin "AC1") (pinfunction "AC1_AC1") (pintype "passive"))
      (node (ref "R10") (pin "2") (pinfunction "2_2") (pintype "passive"))
      (node (ref "X1") (pin "3") (pinfunction "3_3") (pintype "passive"))
    )
    (net (code "91") (name "Net-(B3-Pad+)") (class "Default")
      (node (ref "B3") (pin "+") (pinfunction "+_+") (pintype "passive"))
      (node (ref "B3") (pin "-") (pinfunction "-_-") (pintype "passive"))
    )
    (net (code "92") (name "Net-(B3-PadAC1)") (class "Default")
      (node (ref "B3") (pin "AC1") (pinfunction "AC1_AC1") (pintype "passive"))
      (node (ref "R11") (pin "2") (pinfunction "2_2") (pintype "passive"))
      (node (ref "X1") (pin "4") (pinfunction "4_4") (pintype "passive"))
    )
    (net (code "93") (name "Net-(B4-Pad+)") (class "Default")
      (node (ref "B4") (pin "+") (pinfunction "+_+") (pintype "passive"))
      (node (ref "B4") (pin "-") (pinfunction "-_-") (pintype "passive"))
    )
    (net (code "94") (name "Net-(B4-PadAC1)") (class "Default")
      (node (ref "B4") (pin "AC1") (pinfunction "AC1_AC1") (pintype "passive"))
      (node (ref "R12") (pin "2") (pinfunction "2_2") (pintype "passive"))
      (node (ref "X1") (pin "5") (pinfunction "5_5") (pintype "passive"))
    )
    (net (code "95") (name "Net-(B5-Pad+)") (class "Default")
      (node (ref "B5") (pin "+") (pinfunction "+_+") (pintype "passive"))
      (node (ref "B5") (pin "-") (pinfunction "-_-") (pintype "passive"))
    )
    (net (code "96") (name "Net-(B5-PadAC1)") (class "Default")
      (node (ref "B5") (pin "AC1") (pinfunction "AC1_AC1") (pintype "passive"))
      (node (ref "R13") (pin "2") (pinfunction "2_2") (pintype "passive"))
      (node (ref "X1") (pin "6") (pinfunction "6_6") (pintype "passive"))
    )
    (net (code "97") (name "Net-(B6-Pad+)") (class "Default")
      (node (ref "B6") (pin "+") (pinfunction "+_+") (pintype "passive"))
      (node (ref "B6") (pin "-") (pinfunction "-_-") (pintype "passive"))
    )
    (net (code "98") (name "Net-(B6-PadAC1)") (class "Default")
      (node (ref "B6") (pin "AC1") (pinfunction "AC1_AC1") (pintype "passive"))
      (node (ref "R14") (pin "2") (pinfunction "2_2") (pintype "passive"))
      (node (ref "X1") (pin "7") (pinfunction "7_7") (pintype "passive"))
    )
    (net (code "99") (name "Net-(B7-Pad+)") (class "Default")
      (node (ref "B7") (pin "+") (pinfunction "+_+") (pintype "passive"))
      (node (ref "B7") (pin "-") (pinfunction "-_-") (pintype "passive"))
    )
    (net (code "100") (name "Net-(B7-PadAC1)") (class "Default")
      (node (ref "B7") (pin "AC1") (pinfunction "AC1_AC1") (pintype "passive"))
      (node (ref "R15") (pin "2") (pinfunction "2_2") (pintype "passive"))
      (node (ref "X1") (pin "8") (pinfunction "8_8") (pintype "passive"))
    )
    (net (code "101") (name "Net-(B8-Pad+)") (class "Default")
      (node (ref "B8") (pin "+") (pinfunction "+_+") (pintype "passive"))
      (node (ref "B8") (pin "-") (pinfunction "-_-") (pintype "passive"))
    )
    (net (code "102") (name "Net-(B8-PadAC1)") (class "Default")
      (node (ref "B8") (pin "AC1") (pinfunction "AC1_AC1") (pintype "passive"))
      (node (ref "R16") (pin "2") (pinfunction "2_2") (pintype "passive"))
      (node (ref "X1") (pin "9") (pinfunction "9_9") (pintype "passive"))
    )
    (net (code "103") (name "Net-(B9-Pad+)") (class "Default")
      (node (ref "B9") (pin "+") (pinfunction "+_+") (pintype "passive"))
      (node (ref "B9") (pin "-") (pinfunction "-_-") (pintype "passive"))
    )
    (net (code "104") (name "Net-(B9-PadAC1)") (class "Default")
      (node (ref "B9") (pin "AC1") (pinfunction "AC1_AC1") (pintype "passive"))
      (node (ref "R17") (pin "2") (pinfunction "2_2") (pintype "passive"))
      (node (ref "X2") (pin "2") (pinfunction "2_2") (pintype "passive"))
    )
    (net (code "105") (name "Net-(B10-Pad+)") (class "Default")
      (node (ref "B10") (pin "+") (pinfunction "+_+") (pintype "passive"))
      (node (ref "B10") (pin "-") (pinfunction "-_-") (pintype "passive"))
    )
    (net (code "106") (name "Net-(B10-PadAC1)") (class "Default")
      (node (ref "B10") (pin "AC1") (pinfunction "AC1_AC1") (pintype "passive"))
      (node (ref "R18") (pin "2") (pinfunction "2_2") (pintype "passive"))
      (node (ref "X2") (pin "3") (pinfunction "3_3") (pintype "passive"))
    )
    (net (code "107") (name "Net-(B11-Pad+)") (class "Default")
      (node (ref "B11") (pin "+") (pinfunction "+_+") (pintype "passive"))
      (node (ref "B11") (pin "-") (pinfunction "-_-") (pintype "passive"))
    )
    (net (code "108") (name "Net-(B11-PadAC1)") (class "Default")
      (node (ref "B11") (pin "AC1") (pinfunction "AC1_AC1") (pintype "passive"))
      (node (ref "R19") (pin "2") (pinfunction "2_2") (pintype "passive"))
      (node (ref "X2") (pin "4") (pinfunction "4_4") (pintype "passive"))
    )
    (net (code "109") (name "Net-(B12-Pad+)") (class "Default")
      (node (ref "B12") (pin "+") (pinfunction "+_+") (pintype "passive"))
      (node (ref "B12") (pin "-") (pinfunction "-_-") (pintype "passive"))
    )
    (net (code "110") (name "Net-(B12-PadAC1)") (class "Default")
      (node (ref "B12") (pin "AC1") (pinfunction "AC1_AC1") (pintype "passive"))
      (node (ref "R20") (pin "2") (pinfunction "2_2") (pintype "passive"))
      (node (ref "X2") (pin "5") (pinfunction "5_5") (pintype "passive"))
    )
    (net (code "111") (name "Net-(B13-Pad+)") (class "Default")
      (node (ref "B13") (pin "+") (pinfunction "+_+") (pintype "passive"))
      (node (ref "B13") (pin "-") (pinfunction "-_-") (pintype "passive"))
    )
    (net (code "112") (name "Net-(B13-PadAC1)") (class "Default")
      (node (ref "B13") (pin "AC1") (pinfunction "AC1_AC1") (pintype "passive"))
      (node (ref "R21") (pin "2") (pinfunction "2_2") (pintype "passive"))
      (node (ref "X2") (pin "6") (pinfunction "6_6") (pintype "passive"))
    )
    (net (code "113") (name "Net-(B14-Pad+)") (class "Default")
      (node (ref "B14") (pin "+") (pinfunction "+_+") (pintype "passive"))
      (node (ref "B14") (pin "-") (pinfunction "-_-") (pintype "passive"))
    )
    (net (code "114") (name "Net-(B14-PadAC1)") (class "Default")
      (node (ref "B14") (pin "AC1") (pinfunction "AC1_AC1") (pintype "passive"))
      (node (ref "R22") (pin "2") (pinfunction "2_2") (pintype "passive"))
      (node (ref "X2") (pin "7") (pinfunction "7_7") (pintype "passive"))
    )
    (net (code "115") (name "Net-(B15-Pad+)") (class "Default")
      (node (ref "B15") (pin "+") (pinfunction "+_+") (pintype "passive"))
      (node (ref "B15") (pin "-") (pinfunction "-_-") (pintype "passive"))
    )
    (net (code "116") (name "Net-(B15-PadAC1)") (class "Default")
      (node (ref "B15") (pin "AC1") (pinfunction "AC1_AC1") (pintype "passive"))
      (node (ref "R23") (pin "2") (pinfunction "2_2") (pintype "passive"))
      (node (ref "X2") (pin "8") (pinfunction "8_8") (pintype "passive"))
    )
    (net (code "117") (name "Net-(B16-Pad+)") (class "Default")
      (node (ref "B16") (pin "+") (pinfunction "+_+") (pintype "passive"))
      (node (ref "B16") (pin "-") (pinfunction "-_-") (pintype "passive"))
    )
    (net (code "118") (name "Net-(B16-PadAC1)") (class "Default")
      (node (ref "B16") (pin "AC1") (pinfunction "AC1_AC1") (pintype "passive"))
      (node (ref "R24") (pin "2") (pinfunction "2_2") (pintype "passive"))
      (node (ref "X2") (pin "9") (pinfunction "9_9") (pintype "passive"))
    )
    (net (code "119") (name "Net-(B17-Pad+)") (class "Default")
      (node (ref "B17") (pin "+") (pinfunction "+_+") (pintype "passive"))
      (node (ref "B17") (pin "-") (pinfunction "-_-") (pintype "passive"))
    )
    (net (code "120") (name "Net-(B17-PadAC1)") (class "Default")
      (node (ref "B17") (pin "AC1") (pinfunction "AC1_AC1") (pintype "passive"))
      (node (ref "R25") (pin "2") (pinfunction "2_2") (pintype "passive"))
      (node (ref "X3") (pin "2") (pinfunction "2_2") (pintype "passive"))
    )
    (net (code "121") (name "Net-(B18-Pad+)") (class "Default")
      (node (ref "B18") (pin "+") (pinfunction "+_+") (pintype "passive"))
      (node (ref "B18") (pin "-") (pinfunction "-_-") (pintype "passive"))
    )
    (net (code "122") (name "Net-(B18-PadAC1)") (class "Default")
      (node (ref "B18") (pin "AC1") (pinfunction "AC1_AC1") (pintype "passive"))
      (node (ref "R26") (pin "2") (pinfunction "2_2") (pintype "passive"))
      (node (ref "X3") (pin "3") (pinfunction "3_3") (pintype "passive"))
    )
    (net (code "123") (name "Net-(B19-Pad+)") (class "Default")
      (node (ref "B19") (pin "+") (pinfunction "+_+") (pintype "passive"))
      (node (ref "B19") (pin "-") (pinfunction "-_-") (pintype "passive"))
    )
    (net (code "124") (name "Net-(B19-PadAC1)") (class "Default")
      (node (ref "B19") (pin "AC1") (pinfunction "AC1_AC1") (pintype "passive"))
      (node (ref "R27") (pin "2") (pinfunction "2_2") (pintype "passive"))
      (node (ref "X3") (pin "4") (pinfunction "4_4") (pintype "passive"))
    )
    (net (code "125") (name "Net-(B20-Pad+)") (class "Default")
      (node (ref "B20") (pin "+") (pinfunction "+_+") (pintype "passive"))
      (node (ref "B20") (pin "-") (pinfunction "-_-") (pintype "passive"))
    )
    (net (code "126") (name "Net-(B20-PadAC1)") (class "Default")
      (node (ref "B20") (pin "AC1") (pinfunction "AC1_AC1") (pintype "passive"))
      (node (ref "R28") (pin "2") (pinfunction "2_2") (pintype "passive"))
      (node (ref "X3") (pin "5") (pinfunction "5_5") (pintype "passive"))
    )
    (net (code "127") (name "Net-(B21-Pad+)") (class "Default")
      (node (ref "B21") (pin "+") (pinfunction "+_+") (pintype "passive"))
      (node (ref "B21") (pin "-") (pinfunction "-_-") (pintype "passive"))
    )
    (net (code "128") (name "Net-(B21-PadAC1)") (class "Default")
      (node (ref "B21") (pin "AC1") (pinfunction "AC1_AC1") (pintype "passive"))
      (node (ref "R29") (pin "2") (pinfunction "2_2") (pintype "passive"))
      (node (ref "X3") (pin "6") (pinfunction "6_6") (pintype "passive"))
    )
    (net (code "129") (name "Net-(B22-Pad+)") (class "Default")
      (node (ref "B22") (pin "+") (pinfunction "+_+") (pintype "passive"))
      (node (ref "B22") (pin "-") (pinfunction "-_-") (pintype "passive"))
    )
    (net (code "130") (name "Net-(B22-PadAC1)") (class "Default")
      (node (ref "B22") (pin "AC1") (pinfunction "AC1_AC1") (pintype "passive"))
      (node (ref "R30") (pin "2") (pinfunction "2_2") (pintype "passive"))
      (node (ref "X3") (pin "7") (pinfunction "7_7") (pintype "passive"))
    )
    (net (code "131") (name "Net-(B23-Pad+)") (class "Default")
      (node (ref "B23") (pin "+") (pinfunction "+_+") (pintype "passive"))
      (node (ref "B23") (pin "-") (pinfunction "-_-") (pintype "passive"))
    )
    (net (code "132") (name "Net-(B23-PadAC1)") (class "Default")
      (node (ref "B23") (pin "AC1") (pinfunction "AC1_AC1") (pintype "passive"))
      (node (ref "R31") (pin "2") (pinfunction "2_2") (pintype "passive"))
      (node (ref "X3") (pin "8") (pinfunction "8_8") (pintype "passive"))
    )
    (net (code "133") (name "Net-(B24-Pad+)") (class "Default")
      (node (ref "B24") (pin "+") (pinfunction "+_+") (pintype "passive"))
      (node (ref "B24") (pin "-") (pinfunction "-_-") (pintype "passive"))
    )
    (net (code "134") (name "Net-(B24-PadAC1)") (class "Default")
      (node (ref "B24") (pin "AC1") (pinfunction "AC1_AC1") (pintype "passive"))
      (node (ref "R32") (pin "2") (pinfunction "2_2") (pintype "passive"))
      (node (ref "X3") (pin "9") (pinfunction "9_9") (pintype "passive"))
    )
    (net (code "135") (name "Net-(B25-Pad+)") (class "Default")
      (node (ref "B25") (pin "+") (pinfunction "+_+") (pintype "passive"))
      (node (ref "B25") (pin "-") (pinfunction "-_-") (pintype "passive"))
    )
    (net (code "136") (name "Net-(B25-PadAC1)") (class "Default")
      (node (ref "B25") (pin "AC1") (pinfunction "AC1_AC1") (pintype "passive"))
      (node (ref "R33") (pin "2") (pinfunction "2_2") (pintype "passive"))
      (node (ref "X4") (pin "2") (pinfunction "2_2") (pintype "passive"))
    )
    (net (code "137") (name "Net-(B26-Pad+)") (class "Default")
      (node (ref "B26") (pin "+") (pinfunction "+_+") (pintype "passive"))
      (node (ref "B26") (pin "-") (pinfunction "-_-") (pintype "passive"))
    )
    (net (code "138") (name "Net-(B26-PadAC1)") (class "Default")
      (node (ref "B26") (pin "AC1") (pinfunction "AC1_AC1") (pintype "passive"))
      (node (ref "R34") (pin "2") (pinfunction "2_2") (pintype "passive"))
      (node (ref "X4") (pin "3") (pinfunction "3_3") (pintype "passive"))
    )
    (net (code "139") (name "Net-(B27-Pad+)") (class "Default")
      (node (ref "B27") (pin "+") (pinfunction "+_+") (pintype "passive"))
      (node (ref "B27") (pin "-") (pinfunction "-_-") (pintype "passive"))
    )
    (net (code "140") (name "Net-(B27-PadAC1)") (class "Default")
      (node (ref "B27") (pin "AC1") (pinfunction "AC1_AC1") (pintype "passive"))
      (node (ref "R35") (pin "2") (pinfunction "2_2") (pintype "passive"))
      (node (ref "X4") (pin "4") (pinfunction "4_4") (pintype "passive"))
    )
    (net (code "141") (name "Net-(B28-Pad+)") (class "Default")
      (node (ref "B28") (pin "+") (pinfunction "+_+") (pintype "passive"))
      (node (ref "B28") (pin "-") (pinfunction "-_-") (pintype "passive"))
    )
    (net (code "142") (name "Net-(B28-PadAC1)") (class "Default")
      (node (ref "B28") (pin "AC1") (pinfunction "AC1_AC1") (pintype "passive"))
      (node (ref "R36") (pin "2") (pinfunction "2_2") (pintype "passive"))
      (node (ref "X4") (pin "5") (pinfunction "5_5") (pintype "passive"))
    )
    (net (code "143") (name "Net-(B29-Pad+)") (class "Default")
      (node (ref "B29") (pin "+") (pinfunction "+_+") (pintype "passive"))
      (node (ref "B29") (pin "-") (pinfunction "-_-") (pintype "passive"))
    )
    (net (code "144") (name "Net-(B29-PadAC1)") (class "Default")
      (node (ref "B29") (pin "AC1") (pinfunction "AC1_AC1") (pintype "passive"))
      (node (ref "R37") (pin "2") (pinfunction "2_2") (pintype "passive"))
      (node (ref "X4") (pin "6") (pinfunction "6_6") (pintype "passive"))
    )
    (net (code "145") (name "Net-(B30-Pad+)") (class "Default")
      (node (ref "B30") (pin "+") (pinfunction "+_+") (pintype "passive"))
      (node (ref "B30") (pin "-") (pinfunction "-_-") (pintype "passive"))
    )
    (net (code "146") (name "Net-(B30-PadAC1)") (class "Default")
      (node (ref "B30") (pin "AC1") (pinfunction "AC1_AC1") (pintype "passive"))
      (node (ref "R38") (pin "2") (pinfunction "2_2") (pintype "passive"))
      (node (ref "X4") (pin "7") (pinfunction "7_7") (pintype "passive"))
    )
    (net (code "147") (name "Net-(B31-Pad+)") (class "Default")
      (node (ref "B31") (pin "+") (pinfunction "+_+") (pintype "passive"))
      (node (ref "B31") (pin "-") (pinfunction "-_-") (pintype "passive"))
    )
    (net (code "148") (name "Net-(B31-PadAC1)") (class "Default")
      (node (ref "B31") (pin "AC1") (pinfunction "AC1_AC1") (pintype "passive"))
      (node (ref "R39") (pin "2") (pinfunction "2_2") (pintype "passive"))
      (node (ref "X4") (pin "8") (pinfunction "8_8") (pintype "passive"))
    )
    (net (code "149") (name "Net-(B32-Pad+)") (class "Default")
      (node (ref "B32") (pin "+") (pinfunction "+_+") (pintype "passive"))
      (node (ref "B32") (pin "-") (pinfunction "-_-") (pintype "passive"))
    )
    (net (code "150") (name "Net-(B32-PadAC1)") (class "Default")
      (node (ref "B32") (pin "AC1") (pinfunction "AC1_AC1") (pintype "passive"))
      (node (ref "R40") (pin "2") (pinfunction "2_2") (pintype "passive"))
      (node (ref "X4") (pin "9") (pinfunction "9_9") (pintype "passive"))
    )
    (net (code "151") (name "Net-(IC1-(ICP1)_PD4)") (class "Default")
      (node (ref "IC1") (pin "47") (pinfunction "(ICP1)_PD4_47") (pintype "bidirectional"))
      (node (ref "S1") (pin "8") (pinfunction "8_8") (pintype "passive"))
    )
    (net (code "152") (name "Net-(IC1-(T0)_PD7)") (class "Default")
      (node (ref "IC1") (pin "50") (pinfunction "(T0)_PD7_50") (pintype "bidirectional"))
      (node (ref "S1") (pin "5") (pinfunction "5_5") (pintype "passive"))
    )
    (net (code "153") (name "Net-(IC1-(T1)_PD6)") (class "Default")
      (node (ref "IC1") (pin "49") (pinfunction "(T1)_PD6_49") (pintype "bidirectional"))
      (node (ref "S1") (pin "6") (pinfunction "6_6") (pintype "passive"))
    )
    (net (code "154") (name "Net-(IC1-(XCK1)_PD5)") (class "Default")
      (node (ref "IC1") (pin "48") (pinfunction "(XCK1)_PD5_48") (pintype "bidirectional"))
      (node (ref "S1") (pin "7") (pinfunction "7_7") (pintype "passive"))
    )
    (net (code "155") (name "Net-(IC4-PC0)") (class "Default")
      (node (ref "C44") (pin "1") (pinfunction "1_1") (pintype "passive"))
      (node (ref "IC4") (pin "2") (pinfunction "PC0_2") (pintype "bidirectional"))
      (node (ref "Q3") (pin "3") (pinfunction "2_3") (pintype "passive"))
      (node (ref "R41") (pin "2") (pinfunction "2_2") (pintype "passive"))
    )
    (net (code "156") (name "Net-(IC4-UCAP)") (class "Default")
      (node (ref "C45") (pin "1") (pinfunction "1_1") (pintype "passive"))
      (node (ref "IC4") (pin "27") (pinfunction "UCAP_27") (pintype "output"))
    )
    (net (code "157") (name "Net-(IC4-XTAL1)") (class "Default")
      (node (ref "C43") (pin "1") (pinfunction "1_1") (pintype "passive"))
      (node (ref "IC4") (pin "1") (pinfunction "XTAL1_1") (pintype "input"))
      (node (ref "Q3") (pin "1") (pinfunction "1_1") (pintype "passive"))
      (node (ref "R41") (pin "1") (pinfunction "1_1") (pintype "passive"))
    )
    (net (code "158") (name "Net-(J1-Pad1)") (class "Default")
      (node (ref "J1") (pin "1") (pinfunction "1_1") (pintype "passive"))
      (node (ref "J2") (pin "1") (pinfunction "1_1") (pintype "passive"))
    )
    (net (code "159") (name "Net-(J1-Pad2)") (class "Default")
      (node (ref "J1") (pin "2") (pinfunction "2_2") (pintype "passive"))
      (node (ref "J2") (pin "2") (pinfunction "2_2") (pintype "passive"))
    )
    (net (code "160") (name "Net-(OK1A-A)") (class "Default")
      (node (ref "C14") (pin "1") (pinfunction "1_1") (pintype "passive"))
      (node (ref "OK1") (pin "1") (pinfunction "A_1") (pintype "passive"))
      (node (ref "R12") (pin "1") (pinfunction "1_1") (pintype "passive"))
    )
    (net (code "161") (name "Net-(OK1B-A)") (class "Default")
      (node (ref "C13") (pin "1") (pinfunction "1_1") (pintype "passive"))
      (node (ref "OK1") (pin "3") (pinfunction "A_3") (pintype "passive"))
      (node (ref "R11") (pin "1") (pinfunction "1_1") (pintype "passive"))
    )
    (net (code "162") (name "Net-(OK1C-A)") (class "Default")
      (node (ref "C12") (pin "1") (pinfunction "1_1") (pintype "passive"))
      (node (ref "OK1") (pin "5") (pinfunction "A_5") (pintype "passive"))
      (node (ref "R10") (pin "1") (pinfunction "1_1") (pintype "passive"))
    )
    (net (code "163") (name "Net-(OK1D-A)") (class "Default")
      (node (ref "C11") (pin "1") (pinfunction "1_1") (pintype "passive"))
      (node (ref "OK1") (pin "7") (pinfunction "A_7") (pintype "passive"))
      (node (ref "R9") (pin "1") (pinfunction "1_1") (pintype "passive"))
    )
    (net (code "164") (name "Net-(OK2A-A)") (class "Default")
      (node (ref "C18") (pin "1") (pinfunction "1_1") (pintype "passive"))
      (node (ref "OK2") (pin "1") (pinfunction "A_1") (pintype "passive"))
      (node (ref "R16") (pin "1") (pinfunction "1_1") (pintype "passive"))
    )
    (net (code "165") (name "Net-(OK2B-A)") (class "Default")
      (node (ref "C17") (pin "1") (pinfunction "1_1") (pintype "passive"))
      (node (ref "OK2") (pin "3") (pinfunction "A_3") (pintype "passive"))
      (node (ref "R15") (pin "1") (pinfunction "1_1") (pintype "passive"))
    )
    (net (code "166") (name "Net-(OK2C-A)") (class "Default")
      (node (ref "C16") (pin "1") (pinfunction "1_1") (pintype "passive"))
      (node (ref "OK2") (pin "5") (pinfunction "A_5") (pintype "passive"))
      (node (ref "R14") (pin "1") (pinfunction "1_1") (pintype "passive"))
    )
    (net (code "167") (name "Net-(OK2D-A)") (class "Default")
      (node (ref "C15") (pin "1") (pinfunction "1_1") (pintype "passive"))
      (node (ref "OK2") (pin "7") (pinfunction "A_7") (pintype "passive"))
      (node (ref "R13") (pin "1") (pinfunction "1_1") (pintype "passive"))
    )
    (net (code "168") (name "Net-(OK3A-A)") (class "Default")
      (node (ref "C22") (pin "1") (pinfunction "1_1") (pintype "passive"))
      (node (ref "OK3") (pin "1") (pinfunction "A_1") (pintype "passive"))
      (node (ref "R20") (pin "1") (pinfunction "1_1") (pintype "passive"))
    )
    (net (code "169") (name "Net-(OK3B-A)") (class "Default")
      (node (ref "C21") (pin "1") (pinfunction "1_1") (pintype "passive"))
      (node (ref "OK3") (pin "3") (pinfunction "A_3") (pintype "passive"))
      (node (ref "R19") (pin "1") (pinfunction "1_1") (pintype "passive"))
    )
    (net (code "170") (name "Net-(OK3C-A)") (class "Default")
      (node (ref "C20") (pin "1") (pinfunction "1_1") (pintype "passive"))
      (node (ref "OK3") (pin "5") (pinfunction "A_5") (pintype "passive"))
      (node (ref "R18") (pin "1") (pinfunction "1_1") (pintype "passive"))
    )
    (net (code "171") (name "Net-(OK3D-A)") (class "Default")
      (node (ref "C19") (pin "1") (pinfunction "1_1") (pintype "passive"))
      (node (ref "OK3") (pin "7") (pinfunction "A_7") (pintype "passive"))
      (node (ref "R17") (pin "1") (pinfunction "1_1") (pintype "passive"))
    )
    (net (code "172") (name "Net-(OK4A-A)") (class "Default")
      (node (ref "C26") (pin "1") (pinfunction "1_1") (pintype "passive"))
      (node (ref "OK4") (pin "1") (pinfunction "A_1") (pintype "passive"))
      (node (ref "R24") (pin "1") (pinfunction "1_1") (pintype "passive"))
    )
    (net (code "173") (name "Net-(OK4B-A)") (class "Default")
      (node (ref "C25") (pin "1") (pinfunction "1_1") (pintype "passive"))
      (node (ref "OK4") (pin "3") (pinfunction "A_3") (pintype "passive"))
      (node (ref "R23") (pin "1") (pinfunction "1_1") (pintype "passive"))
    )
    (net (code "174") (name "Net-(OK4C-A)") (class "Default")
      (node (ref "C24") (pin "1") (pinfunction "1_1") (pintype "passive"))
      (node (ref "OK4") (pin "5") (pinfunction "A_5") (pintype "passive"))
      (node (ref "R22") (pin "1") (pinfunction "1_1") (pintype "passive"))
    )
    (net (code "175") (name "Net-(OK4D-A)") (class "Default")
      (node (ref "C23") (pin "1") (pinfunction "1_1") (pintype "passive"))
      (node (ref "OK4") (pin "7") (pinfunction "A_7") (pintype "passive"))
      (node (ref "R21") (pin "1") (pinfunction "1_1") (pintype "passive"))
    )
    (net (code "176") (name "Net-(OK5A-A)") (class "Default")
      (node (ref "C30") (pin "1") (pinfunction "1_1") (pintype "passive"))
      (node (ref "OK5") (pin "1") (pinfunction "A_1") (pintype "passive"))
      (node (ref "R28") (pin "1") (pinfunction "1_1") (pintype "passive"))
    )
    (net (code "177") (name "Net-(OK5B-A)") (class "Default")
      (node (ref "C29") (pin "1") (pinfunction "1_1") (pintype "passive"))
      (node (ref "OK5") (pin "3") (pinfunction "A_3") (pintype "passive"))
      (node (ref "R27") (pin "1") (pinfunction "1_1") (pintype "passive"))
    )
    (net (code "178") (name "Net-(OK5C-A)") (class "Default")
      (node (ref "C28") (pin "1") (pinfunction "1_1") (pintype "passive"))
      (node (ref "OK5") (pin "5") (pinfunction "A_5") (pintype "passive"))
      (node (ref "R26") (pin "1") (pinfunction "1_1") (pintype "passive"))
    )
    (net (code "179") (name "Net-(OK5D-A)") (class "Default")
      (node (ref "C27") (pin "1") (pinfunction "1_1") (pintype "passive"))
      (node (ref "OK5") (pin "7") (pinfunction "A_7") (pintype "passive"))
      (node (ref "R25") (pin "1") (pinfunction "1_1") (pintype "passive"))
    )
    (net (code "180") (name "Net-(OK6A-A)") (class "Default")
      (node (ref "C34") (pin "1") (pinfunction "1_1") (pintype "passive"))
      (node (ref "OK6") (pin "1") (pinfunction "A_1") (pintype "passive"))
      (node (ref "R32") (pin "1") (pinfunction "1_1") (pintype "passive"))
    )
    (net (code "181") (name "Net-(OK6B-A)") (class "Default")
      (node (ref "C33") (pin "1") (pinfunction "1_1") (pintype "passive"))
      (node (ref "OK6") (pin "3") (pinfunction "A_3") (pintype "passive"))
      (node (ref "R31") (pin "1") (pinfunction "1_1") (pintype "passive"))
    )
    (net (code "182") (name "Net-(OK6C-A)") (class "Default")
      (node (ref "C32") (pin "1") (pinfunction "1_1") (pintype "passive"))
      (node (ref "OK6") (pin "5") (pinfunction "A_5") (pintype "passive"))
      (node (ref "R30") (pin "1") (pinfunction "1_1") (pintype "passive"))
    )
    (net (code "183") (name "Net-(OK6D-A)") (class "Default")
      (node (ref "C31") (pin "1") (pinfunction "1_1") (pintype "passive"))
      (node (ref "OK6") (pin "7") (pinfunction "A_7") (pintype "passive"))
      (node (ref "R29") (pin "1") (pinfunction "1_1") (pintype "passive"))
    )
    (net (code "184") (name "Net-(OK7A-A)") (class "Default")
      (node (ref "C38") (pin "1") (pinfunction "1_1") (pintype "passive"))
      (node (ref "OK7") (pin "1") (pinfunction "A_1") (pintype "passive"))
      (node (ref "R36") (pin "1") (pinfunction "1_1") (pintype "passive"))
    )
    (net (code "185") (name "Net-(OK7B-A)") (class "Default")
      (node (ref "C37") (pin "1") (pinfunction "1_1") (pintype "passive"))
      (node (ref "OK7") (pin "3") (pinfunction "A_3") (pintype "passive"))
      (node (ref "R35") (pin "1") (pinfunction "1_1") (pintype "passive"))
    )
    (net (code "186") (name "Net-(OK7C-A)") (class "Default")
      (node (ref "C36") (pin "1") (pinfunction "1_1") (pintype "passive"))
      (node (ref "OK7") (pin "5") (pinfunction "A_5") (pintype "passive"))
      (node (ref "R34") (pin "1") (pinfunction "1_1") (pintype "passive"))
    )
    (net (code "187") (name "Net-(OK7D-A)") (class "Default")
      (node (ref "C35") (pin "1") (pinfunction "1_1") (pintype "passive"))
      (node (ref "OK7") (pin "7") (pinfunction "A_7") (pintype "passive"))
      (node (ref "R33") (pin "1") (pinfunction "1_1") (pintype "passive"))
    )
    (net (code "188") (name "Net-(OK8A-A)") (class "Default")
      (node (ref "C42") (pin "1") (pinfunction "1_1") (pintype "passive"))
      (node (ref "OK8") (pin "1") (pinfunction "A_1") (pintype "passive"))
      (node (ref "R40") (pin "1") (pinfunction "1_1") (pintype "passive"))
    )
    (net (code "189") (name "Net-(OK8B-A)") (class "Default")
      (node (ref "C41") (pin "1") (pinfunction "1_1") (pintype "passive"))
      (node (ref "OK8") (pin "3") (pinfunction "A_3") (pintype "passive"))
      (node (ref "R39") (pin "1") (pinfunction "1_1") (pintype "passive"))
    )
    (net (code "190") (name "Net-(OK8C-A)") (class "Default")
      (node (ref "C40") (pin "1") (pinfunction "1_1") (pintype "passive"))
      (node (ref "OK8") (pin "5") (pinfunction "A_5") (pintype "passive"))
      (node (ref "R38") (pin "1") (pinfunction "1_1") (pintype "passive"))
    )
    (net (code "191") (name "Net-(OK8D-A)") (class "Default")
      (node (ref "C39") (pin "1") (pinfunction "1_1") (pintype "passive"))
      (node (ref "OK8") (pin "7") (pinfunction "A_7") (pintype "passive"))
      (node (ref "R37") (pin "1") (pinfunction "1_1") (pintype "passive"))
    )
    (net (code "192") (name "Net-(OK9-C)") (class "Default")
      (node (ref "OK9") (pin "2") (pinfunction "C_2") (pintype "passive"))
      (node (ref "R46") (pin "1") (pinfunction "1_1") (pintype "passive"))
    )
    (net (code "193") (name "Net-(OK9-COL)") (class "Default")
      (node (ref "C46") (pin "1") (pinfunction "1_1") (pintype "passive"))
      (node (ref "OK9") (pin "4") (pinfunction "COL_4") (pintype "passive"))
      (node (ref "R45") (pin "1") (pinfunction "1_1") (pintype "passive"))
    )
    (net (code "194") (name "Net-(POWER-PadC)") (class "Default")
      (node (ref "POWER") (pin "C") (pinfunction "C_C") (pintype "passive"))
      (node (ref "R4") (pin "1") (pinfunction "1_1") (pintype "passive"))
    )
    (net (code "195") (name "Net-(R3-Pad2)") (class "Default")
      (node (ref "R3") (pin "2") (pinfunction "2_2") (pintype "passive"))
      (node (ref "TERM") (pin "1") (pinfunction "1_1") (pintype "passive"))
    )
    (net (code "196") (name "Net-(R5-Pad1)") (class "Default")
      (node (ref "R5") (pin "1") (pinfunction "1_1") (pintype "passive"))
      (node (ref "STATUS") (pin "C") (pinfunction "C_C") (pintype "passive"))
    )
    (net (code "197") (name "Net-(R42-Pad2)") (class "Default")
      (node (ref "R42") (pin "2") (pinfunction "2_2") (pintype "passive"))
      (node (ref "X6") (pin "2") (pinfunction "2_2") (pintype "passive"))
    )
    (net (code "198") (name "Net-(R43-Pad2)") (class "Default")
      (node (ref "R43") (pin "2") (pinfunction "2_2") (pintype "passive"))
      (node (ref "X6") (pin "3") (pinfunction "3_3") (pintype "passive"))
    )
    (net (code "199") (name "Net-(R47-Pad1)") (class "Default")
      (node (ref "R47") (pin "1") (pinfunction "1_1") (pintype "passive"))
      (node (ref "USBRX") (pin "C") (pinfunction "C_C") (pintype "passive"))
    )
    (net (code "200") (name "Net-(R48-Pad1)") (class "Default")
      (node (ref "R48") (pin "1") (pinfunction "1_1") (pintype "passive"))
      (node (ref "USBTX") (pin "C") (pinfunction "C_C") (pintype "passive"))
    )
    (net (code "201") (name "Net-(RN1-Pad1)") (class "Default")
      (node (ref "RN1") (pin "1") (pinfunction "1_1") (pintype "passive"))
      (node (ref "T1") (pin "A") (pinfunction "A_A") (pintype "passive"))
    )
    (net (code "202") (name "Net-(RN1B-1)") (class "Default")
      (node (ref "RN1") (pin "2") (pinfunction "1_2") (pintype "passive"))
      (node (ref "T2") (pin "A") (pinfunction "A_A") (pintype "passive"))
    )
    (net (code "203") (name "Net-(RN1C-1)") (class "Default")
      (node (ref "RN1") (pin "3") (pinfunction "1_3") (pintype "passive"))
      (node (ref "T3") (pin "A") (pinfunction "A_A") (pintype "passive"))
    )
    (net (code "204") (name "Net-(RN1D-1)") (class "Default")
      (node (ref "RN1") (pin "4") (pinfunction "1_4") (pintype "passive"))
      (node (ref "T4") (pin "A") (pinfunction "A_A") (pintype "passive"))
    )
    (net (code "205") (name "Net-(RN2-Pad1)") (class "Default")
      (node (ref "RN2") (pin "1") (pinfunction "1_1") (pintype "passive"))
      (node (ref "T5") (pin "A") (pinfunction "A_A") (pintype "passive"))
    )
    (net (code "206") (name "Net-(RN2B-1)") (class "Default")
      (node (ref "RN2") (pin "2") (pinfunction "1_2") (pintype "passive"))
      (node (ref "T6") (pin "A") (pinfunction "A_A") (pintype "passive"))
    )
    (net (code "207") (name "Net-(RN2C-1)") (class "Default")
      (node (ref "RN2") (pin "3") (pinfunction "1_3") (pintype "passive"))
      (node (ref "T7") (pin "A") (pinfunction "A_A") (pintype "passive"))
    )
    (net (code "208") (name "Net-(RN2D-1)") (class "Default")
      (node (ref "RN2") (pin "4") (pinfunction "1_4") (pintype "passive"))
      (node (ref "T8") (pin "A") (pinfunction "A_A") (pintype "passive"))
    )
    (net (code "209") (name "Net-(RN3-Pad1)") (class "Default")
      (node (ref "RN3") (pin "1") (pinfunction "1_1") (pintype "passive"))
      (node (ref "T9") (pin "A") (pinfunction "A_A") (pintype "passive"))
    )
    (net (code "210") (name "Net-(RN3B-1)") (class "Default")
      (node (ref "RN3") (pin "2") (pinfunction "1_2") (pintype "passive"))
      (node (ref "T10") (pin "A") (pinfunction "A_A") (pintype "passive"))
    )
    (net (code "211") (name "Net-(RN3C-1)") (class "Default")
      (node (ref "RN3") (pin "3") (pinfunction "1_3") (pintype "passive"))
      (node (ref "T11") (pin "A") (pinfunction "A_A") (pintype "passive"))
    )
    (net (code "212") (name "Net-(RN3D-1)") (class "Default")
      (node (ref "RN3") (pin "4") (pinfunction "1_4") (pintype "passive"))
      (node (ref "T12") (pin "A") (pinfunction "A_A") (pintype "passive"))
    )
    (net (code "213") (name "Net-(RN4-Pad1)") (class "Default")
      (node (ref "RN4") (pin "1") (pinfunction "1_1") (pintype "passive"))
      (node (ref "T13") (pin "A") (pinfunction "A_A") (pintype "passive"))
    )
    (net (code "214") (name "Net-(RN4B-1)") (class "Default")
      (node (ref "RN4") (pin "2") (pinfunction "1_2") (pintype "passive"))
      (node (ref "T14") (pin "A") (pinfunction "A_A") (pintype "passive"))
    )
    (net (code "215") (name "Net-(RN4C-1)") (class "Default")
      (node (ref "RN4") (pin "3") (pinfunction "1_3") (pintype "passive"))
      (node (ref "T15") (pin "A") (pinfunction "A_A") (pintype "passive"))
    )
    (net (code "216") (name "Net-(RN4D-1)") (class "Default")
      (node (ref "RN4") (pin "4") (pinfunction "1_4") (pintype "passive"))
      (node (ref "T16") (pin "A") (pinfunction "A_A") (pintype "passive"))
    )
    (net (code "217") (name "Net-(RN5-Pad1)") (class "Default")
      (node (ref "RN5") (pin "1") (pinfunction "1_1") (pintype "passive"))
      (node (ref "T17") (pin "A") (pinfunction "A_A") (pintype "passive"))
    )
    (net (code "218") (name "Net-(RN5B-1)") (class "Default")
      (node (ref "RN5") (pin "2") (pinfunction "1_2") (pintype "passive"))
      (node (ref "T18") (pin "A") (pinfunction "A_A") (pintype "passive"))
    )
    (net (code "219") (name "Net-(RN5C-1)") (class "Default")
      (node (ref "RN5") (pin "3") (pinfunction "1_3") (pintype "passive"))
      (node (ref "T19") (pin "A") (pinfunction "A_A") (pintype "passive"))
    )
    (net (code "220") (name "Net-(RN5D-1)") (class "Default")
      (node (ref "RN5") (pin "4") (pinfunction "1_4") (pintype "passive"))
      (node (ref "T20") (pin "A") (pinfunction "A_A") (pintype "passive"))
    )
    (net (code "221") (name "Net-(RN6-Pad1)") (class "Default")
      (node (ref "RN6") (pin "1") (pinfunction "1_1") (pintype "passive"))
      (node (ref "T21") (pin "A") (pinfunction "A_A") (pintype "passive"))
    )
    (net (code "222") (name "Net-(RN6B-1)") (class "Default")
      (node (ref "RN6") (pin "2") (pinfunction "1_2") (pintype "passive"))
      (node (ref "T22") (pin "A") (pinfunction "A_A") (pintype "passive"))
    )
    (net (code "223") (name "Net-(RN6C-1)") (class "Default")
      (node (ref "RN6") (pin "3") (pinfunction "1_3") (pintype "passive"))
      (node (ref "T23") (pin "A") (pinfunction "A_A") (pintype "passive"))
    )
    (net (code "224") (name "Net-(RN6D-1)") (class "Default")
      (node (ref "RN6") (pin "4") (pinfunction "1_4") (pintype "passive"))
      (node (ref "T24") (pin "A") (pinfunction "A_A") (pintype "passive"))
    )
    (net (code "225") (name "Net-(RN7-Pad1)") (class "Default")
      (node (ref "RN7") (pin "1") (pinfunction "1_1") (pintype "passive"))
      (node (ref "T25") (pin "A") (pinfunction "A_A") (pintype "passive"))
    )
    (net (code "226") (name "Net-(RN7B-1)") (class "Default")
      (node (ref "RN7") (pin "2") (pinfunction "1_2") (pintype "passive"))
      (node (ref "T26") (pin "A") (pinfunction "A_A") (pintype "passive"))
    )
    (net (code "227") (name "Net-(RN7C-1)") (class "Default")
      (node (ref "RN7") (pin "3") (pinfunction "1_3") (pintype "passive"))
      (node (ref "T27") (pin "A") (pinfunction "A_A") (pintype "passive"))
    )
    (net (code "228") (name "Net-(RN7D-1)") (class "Default")
      (node (ref "RN7") (pin "4") (pinfunction "1_4") (pintype "passive"))
      (node (ref "T28") (pin "A") (pinfunction "A_A") (pintype "passive"))
    )
    (net (code "229") (name "Net-(RN8-Pad1)") (class "Default")
      (node (ref "RN8") (pin "1") (pinfunction "1_1") (pintype "passive"))
      (node (ref "T29") (pin "A") (pinfunction "A_A") (pintype "passive"))
    )
    (net (code "230") (name "Net-(RN8B-1)") (class "Default")
      (node (ref "RN8") (pin "2") (pinfunction "1_2") (pintype "passive"))
      (node (ref "T30") (pin "A") (pinfunction "A_A") (pintype "passive"))
    )
    (net (code "231") (name "Net-(RN8C-1)") (class "Default")
      (node (ref "RN8") (pin "3") (pinfunction "1_3") (pintype "passive"))
      (node (ref "T31") (pin "A") (pinfunction "A_A") (pintype "passive"))
    )
    (net (code "232") (name "Net-(RN8D-1)") (class "Default")
      (node (ref "RN8") (pin "4") (pinfunction "1_4") (pintype "passive"))
      (node (ref "T32") (pin "A") (pinfunction "A_A") (pintype "passive"))
    )
    (net (code "233") (name "OSC1") (class "Default")
      (node (ref "C7") (pin "1") (pinfunction "1_1") (pintype "passive"))
      (node (ref "IC3") (pin "8") (pinfunction "OSC1_8") (pintype "input"))
      (node (ref "Q2") (pin "1") (pinfunction "1_1") (pintype "passive"))
      (node (ref "R2") (pin "1") (pinfunction "1_1") (pintype "passive"))
    )
    (net (code "234") (name "OSC2") (class "Default")
      (node (ref "C8") (pin "1") (pinfunction "1_1") (pintype "passive"))
      (node (ref "IC3") (pin "7") (pinfunction "OSC2_7") (pintype "output"))
      (node (ref "Q2") (pin "3") (pinfunction "2_3") (pintype "passive"))
      (node (ref "R2") (pin "2") (pinfunction "2_2") (pintype "passive"))
    )
    (net (code "235") (name "RESET") (class "Default")
      (node (ref "C46") (pin "2") (pinfunction "2_2") (pintype "passive"))
      (node (ref "IC1") (pin "30") (pinfunction "~{RESET}_30") (pintype "input"))
      (node (ref "IC3") (pin "17") (pinfunction "~{RESET}_17") (pintype "input"))
      (node (ref "ISP") (pin "5") (pinfunction "S_5") (pintype "passive"))
      (node (ref "R8") (pin "1") (pinfunction "1_1") (pintype "passive"))
      (node (ref "U$15") (pin "P$3") (pinfunction "P$3_P$3") (pintype "bidirectional"))
      (node (ref "U$15") (pin "P$4") (pinfunction "P$4_P$4") (pintype "bidirectional"))
    )
    (net (code "236") (name "RESET2") (class "Default")
      (node (ref "IC4") (pin "24") (pinfunction "PC1//~{RESET}_24") (pintype "bidirectional"))
      (node (ref "R44") (pin "2") (pinfunction "2_2") (pintype "passive"))
      (node (ref "RS") (pin "TP") (pinfunction "TP_TP") (pintype "input"))
    )
    (net (code "237") (name "RXCAN") (class "Default")
      (node (ref "IC2") (pin "4") (pinfunction "RXD_4") (pintype "output"))
      (node (ref "IC3") (pin "2") (pinfunction "RXCAN_2") (pintype "input"))
    )
    (net (code "238") (name "RXD") (class "Default")
      (node (ref "IC1") (pin "2") (pinfunction "(RXD0/PCINT8)_PE0_2") (pintype "bidirectional"))
      (node (ref "IC5") (pin "2") (pinfunction "VOA_2") (pintype "output"))
    )
    (net (code "239") (name "RXDUSB") (class "Default")
      (node (ref "IC4") (pin "8") (pinfunction "PD2_8") (pintype "bidirectional"))
      (node (ref "IC5") (pin "6") (pinfunction "VOB_6") (pintype "output"))
    )
    (net (code "240") (name "RXLED") (class "Default")
      (node (ref "IC4") (pin "10") (pinfunction "PD4_10") (pintype "bidirectional"))
      (node (ref "R47") (pin "2") (pinfunction "2_2") (pintype "passive"))
    )
    (net (code "241") (name "SCK") (class "Default")
      (node (ref "IC1") (pin "20") (pinfunction "(SCK/PCINT1)_PB1_20") (pintype "bidirectional"))
      (node (ref "IC3") (pin "13") (pinfunction "SCK_13") (pintype "input"))
      (node (ref "ISP") (pin "3") (pinfunction "S_3") (pintype "passive"))
    )
    (net (code "242") (name "SCK2") (class "Default")
      (node (ref "IC4") (pin "15") (pinfunction "PB1_15") (pintype "bidirectional"))
      (node (ref "SCK") (pin "TP") (pinfunction "TP_TP") (pintype "input"))
    )
    (net (code "243") (name "SCL") (class "Default")
      (node (ref "IC1") (pin "43") (pinfunction "(SCL/INT0)_PD0_43") (pintype "bidirectional"))
      (node (ref "I²C") (pin "2") (pinfunction "S_2") (pintype "passive"))
      (node (ref "R6") (pin "1") (pinfunction "1_1") (pintype "passive"))
    )
    (net (code "244") (name "SDA") (class "Default")
      (node (ref "IC1") (pin "44") (pinfunction "(SDA/INT1)_PD1_44") (pintype "bidirectional"))
      (node (ref "I²C") (pin "1") (pinfunction "S_1") (pintype "passive"))
      (node (ref "R7") (pin "1") (pinfunction "1_1") (pintype "passive"))
    )
    (net (code "245") (name "STATUS") (class "Default")
      (node (ref "IC1") (pin "46") (pinfunction "(TXD1/INT3)_PD3_46") (pintype "bidirectional"))
      (node (ref "STATUS") (pin "A") (pinfunction "A_A") (pintype "passive"))
    )
    (net (code "246") (name "TXCAN") (class "Default")
      (node (ref "IC2") (pin "1") (pinfunction "TXD_1") (pintype "input"))
      (node (ref "IC3") (pin "1") (pinfunction "TXCAN_1") (pintype "output"))
    )
    (net (code "247") (name "TXD") (class "Default")
      (node (ref "IC1") (pin "3") (pinfunction "(TXD0)_PE1_3") (pintype "bidirectional"))
      (node (ref "IC5") (pin "3") (pinfunction "VIB_3") (pintype "input"))
    )
    (net (code "248") (name "TXDUSB") (class "Default")
      (node (ref "IC4") (pin "9") (pinfunction "PD3_9") (pintype "bidirectional"))
      (node (ref "IC5") (pin "7") (pinfunction "VIA_7") (pintype "input"))
    )
    (net (code "249") (name "TXLED") (class "Default")
      (node (ref "IC4") (pin "11") (pinfunction "PD5_11") (pintype "bidirectional"))
      (node (ref "R48") (pin "2") (pinfunction "2_2") (pintype "passive"))
    )
    (net (code "250") (name "VCC") (class "Default")
      (node (ref "C1") (pin "1") (pinfunction "1_1") (pintype "passive"))
      (node (ref "C10") (pin "1") (pinfunction "1_1") (pintype "passive"))
      (node (ref "C2") (pin "1") (pinfunction "1_1") (pintype "passive"))
      (node (ref "C3") (pin "1") (pinfunction "1_1") (pintype "passive"))
      (node (ref "C6") (pin "1") (pinfunction "1_1") (pintype "passive"))
      (node (ref "IC1") (pin "10") (pinfunction "VCC_3_10") (pintype "power_in"))
      (node (ref "IC1") (pin "100") (pinfunction "AVCC_100") (pintype "power_in"))
      (node (ref "IC1") (pin "31") (pinfunction "VCC_2_31") (pintype "power_in"))
      (node (ref "IC1") (pin "61") (pinfunction "VCC_4_61") (pintype "power_in"))
      (node (ref "IC1") (pin "80") (pinfunction "VCC_80") (pintype "power_in"))
      (node (ref "IC2") (pin "3") (pinfunction "VDD_3") (pintype "power_in"))
      (node (ref "IC2") (pin "5") (pinfunction "VREF_5") (pintype "output"))
      (node (ref "IC3") (pin "18") (pinfunction "VDD_18") (pintype "power_in"))
      (node (ref "IC5") (pin "1") (pinfunction "VDD1_1") (pintype "power_in"))
      (node (ref "IC8") (pin "2") (pinfunction "VO_2") (pintype "passive"))
      (node (ref "ISP") (pin "2") (pinfunction "S_2") (pintype "passive"))
      (node (ref "POWER") (pin "A") (pinfunction "A_A") (pintype "passive"))
      (node (ref "R45") (pin "2") (pinfunction "2_2") (pintype "passive"))
      (node (ref "R6") (pin "2") (pinfunction "2_2") (pintype "passive"))
      (node (ref "R7") (pin "2") (pinfunction "2_2") (pintype "passive"))
      (node (ref "R8") (pin "2") (pinfunction "2_2") (pintype "passive"))
      (node (ref "RN1") (pin "5") (pinfunction "2_5") (pintype "passive"))
      (node (ref "RN1") (pin "6") (pinfunction "2_6") (pintype "passive"))
      (node (ref "RN1") (pin "7") (pinfunction "2_7") (pintype "passive"))
      (node (ref "RN1") (pin "8") (pinfunction "2_8") (pintype "passive"))
      (node (ref "RN2") (pin "5") (pinfunction "2_5") (pintype "passive"))
      (node (ref "RN2") (pin "6") (pinfunction "2_6") (pintype "passive"))
      (node (ref "RN2") (pin "7") (pinfunction "2_7") (pintype "passive"))
      (node (ref "RN2") (pin "8") (pinfunction "2_8") (pintype "passive"))
      (node (ref "RN3") (pin "5") (pinfunction "2_5") (pintype "passive"))
      (node (ref "RN3") (pin "6") (pinfunction "2_6") (pintype "passive"))
      (node (ref "RN3") (pin "7") (pinfunction "2_7") (pintype "passive"))
      (node (ref "RN3") (pin "8") (pinfunction "2_8") (pintype "passive"))
      (node (ref "RN4") (pin "5") (pinfunction "2_5") (pintype "passive"))
      (node (ref "RN4") (pin "6") (pinfunction "2_6") (pintype "passive"))
      (node (ref "RN4") (pin "7") (pinfunction "2_7") (pintype "passive"))
      (node (ref "RN4") (pin "8") (pinfunction "2_8") (pintype "passive"))
      (node (ref "RN5") (pin "5") (pinfunction "2_5") (pintype "passive"))
      (node (ref "RN5") (pin "6") (pinfunction "2_6") (pintype "passive"))
      (node (ref "RN5") (pin "7") (pinfunction "2_7") (pintype "passive"))
      (node (ref "RN5") (pin "8") (pinfunction "2_8") (pintype "passive"))
      (node (ref "RN6") (pin "5") (pinfunction "2_5") (pintype "passive"))
      (node (ref "RN6") (pin "6") (pinfunction "2_6") (pintype "passive"))
      (node (ref "RN6") (pin "7") (pinfunction "2_7") (pintype "passive"))
      (node (ref "RN6") (pin "8") (pinfunction "2_8") (pintype "passive"))
      (node (ref "RN7") (pin "5") (pinfunction "2_5") (pintype "passive"))
      (node (ref "RN7") (pin "6") (pinfunction "2_6") (pintype "passive"))
      (node (ref "RN7") (pin "7") (pinfunction "2_7") (pintype "passive"))
      (node (ref "RN7") (pin "8") (pinfunction "2_8") (pintype "passive"))
      (node (ref "RN8") (pin "5") (pinfunction "2_5") (pintype "passive"))
      (node (ref "RN8") (pin "6") (pinfunction "2_6") (pintype "passive"))
      (node (ref "RN8") (pin "7") (pinfunction "2_7") (pintype "passive"))
      (node (ref "RN8") (pin "8") (pinfunction "2_8") (pintype "passive"))
    )
    (net (code "251") (name "VCC2") (class "Default")
      (node (ref "C47") (pin "1") (pinfunction "1_1") (pintype "passive"))
      (node (ref "IC4") (pin "31") (pinfunction "UVCC_31") (pintype "power_in"))
      (node (ref "IC4") (pin "32") (pinfunction "AVCC_32") (pintype "power_in"))
      (node (ref "IC4") (pin "4") (pinfunction "VCC_4") (pintype "power_in"))
      (node (ref "IC5") (pin "8") (pinfunction "VDD2_8") (pintype "power_in"))
      (node (ref "OK9") (pin "1") (pinfunction "A_1") (pintype "passive"))
      (node (ref "R44") (pin "1") (pinfunction "1_1") (pintype "passive"))
      (node (ref "USBRX") (pin "A") (pinfunction "A_A") (pintype "passive"))
      (node (ref "USBTX") (pin "A") (pinfunction "A_A") (pintype "passive"))
      (node (ref "VCC") (pin "TP") (pinfunction "TP_TP") (pintype "input"))
      (node (ref "X6") (pin "1") (pinfunction "1_1") (pintype "passive"))
    )
    (net (code "252") (name "XTAL1") (class "Default")
      (node (ref "C4") (pin "1") (pinfunction "1_1") (pintype "passive"))
      (node (ref "IC1") (pin "34") (pinfunction "XTAL1_34") (pintype "input"))
      (node (ref "Q1") (pin "1") (pinfunction "1_1") (pintype "passive"))
      (node (ref "R1") (pin "1") (pinfunction "1_1") (pintype "passive"))
    )
    (net (code "253") (name "XTAL2") (class "Default")
      (node (ref "C5") (pin "1") (pinfunction "1_1") (pintype "passive"))
      (node (ref "IC1") (pin "33") (pinfunction "XTAL2_33") (pintype "output"))
      (node (ref "Q1") (pin "3") (pinfunction "2_3") (pintype "passive"))
      (node (ref "R1") (pin "2") (pinfunction "2_2") (pintype "passive"))
    )
    (net (code "254") (name "unconnected-(H1-MOUNT-PadB3,2)") (class "Default")
      (node (ref "H1") (pin "B3,2") (pinfunction "MOUNT_B3,2") (pintype "passive"))
    )
    (net (code "255") (name "unconnected-(H2-MOUNT-PadB3,2)") (class "Default")
      (node (ref "H2") (pin "B3,2") (pinfunction "MOUNT_B3,2") (pintype "passive"))
    )
    (net (code "256") (name "unconnected-(H3-MOUNT-PadB3,2)") (class "Default")
      (node (ref "H3") (pin "B3,2") (pinfunction "MOUNT_B3,2") (pintype "passive"))
    )
    (net (code "257") (name "unconnected-(H4-MOUNT-PadB3,2)") (class "Default")
      (node (ref "H4") (pin "B3,2") (pinfunction "MOUNT_B3,2") (pintype "passive"))
    )
    (net (code "258") (name "unconnected-(H5-MOUNT-PadB3,2)") (class "Default")
      (node (ref "H5") (pin "B3,2") (pinfunction "MOUNT_B3,2") (pintype "passive"))
    )
    (net (code "259") (name "unconnected-(H6-MOUNT-PadB3,2)") (class "Default")
      (node (ref "H6") (pin "B3,2") (pinfunction "MOUNT_B3,2") (pintype "passive"))
    )
    (net (code "260") (name "unconnected-(IC1-(OC0B)_PG5-Pad1)") (class "Default")
      (node (ref "IC1") (pin "1") (pinfunction "(OC0B)_PG5_1") (pintype "bidirectional"))
    )
    (net (code "261") (name "unconnected-(IC1-(OC1A{slash}PCINT5)_PB5-Pad24)") (class "Default")
      (node (ref "IC1") (pin "24") (pinfunction "(OC1A/PCINT5)_PB5_24") (pintype "bidirectional"))
    )
    (net (code "262") (name "unconnected-(IC1-(OC2A{slash}PCINT4)_PB4-Pad23)") (class "Default")
      (node (ref "IC1") (pin "23") (pinfunction "(OC2A/PCINT4)_PB4_23") (pintype "bidirectional"))
    )
    (net (code "263") (name "unconnected-(IC1-(TOSC1)_PG4-Pad29)") (class "Default")
      (node (ref "IC1") (pin "29") (pinfunction "(TOSC1)_PG4_29") (pintype "bidirectional"))
    )
    (net (code "264") (name "unconnected-(IC1-(TOSC2)_PG3-Pad28)") (class "Default")
      (node (ref "IC1") (pin "28") (pinfunction "(TOSC2)_PG3_28") (pintype "bidirectional"))
    )
    (net (code "265") (name "unconnected-(IC1-AREF-Pad98)") (class "Default")
      (node (ref "IC1") (pin "98") (pinfunction "AREF_98") (pintype "input"))
    )
    (net (code "266") (name "unconnected-(IC1-PG0_(~{WR})-Pad51)") (class "Default")
      (node (ref "IC1") (pin "51") (pinfunction "PG0_(~{WR})_51") (pintype "bidirectional"))
    )
    (net (code "267") (name "unconnected-(IC1-PG1_(~{RD})-Pad52)") (class "Default")
      (node (ref "IC1") (pin "52") (pinfunction "PG1_(~{RD})_52") (pintype "bidirectional"))
    )
    (net (code "268") (name "unconnected-(IC1-PG2_(ALE)-Pad70)") (class "Default")
      (node (ref "IC1") (pin "70") (pinfunction "PG2_(ALE)_70") (pintype "bidirectional"))
    )
    (net (code "269") (name "unconnected-(IC3-CLKOUT{slash}SOF-Pad3)") (class "Default")
      (node (ref "IC3") (pin "3") (pinfunction "CLKOUT/SOF_3") (pintype "output"))
    )
    (net (code "270") (name "unconnected-(IC3-~{RX0BF}-Pad11)") (class "Default")
      (node (ref "IC3") (pin "11") (pinfunction "~{RX0BF}_11") (pintype "output"))
    )
    (net (code "271") (name "unconnected-(IC3-~{RX1BF}-Pad10)") (class "Default")
      (node (ref "IC3") (pin "10") (pinfunction "~{RX1BF}_10") (pintype "output"))
    )
    (net (code "272") (name "unconnected-(IC3-~{TX0RTS}-Pad4)") (class "Default")
      (node (ref "IC3") (pin "4") (pinfunction "~{TX0RTS}_4") (pintype "input"))
    )
    (net (code "273") (name "unconnected-(IC3-~{TX1RTS}-Pad5)") (class "Default")
      (node (ref "IC3") (pin "5") (pinfunction "~{TX1RTS}_5") (pintype "input"))
    )
    (net (code "274") (name "unconnected-(IC3-~{TX2RTS}-Pad6)") (class "Default")
      (node (ref "IC3") (pin "6") (pinfunction "~{TX2RTS}_6") (pintype "input"))
    )
    (net (code "275") (name "unconnected-(IC4-PB0-Pad14)") (class "Default")
      (node (ref "IC4") (pin "14") (pinfunction "PB0_14") (pintype "bidirectional"))
    )
    (net (code "276") (name "unconnected-(IC4-PB4-Pad18)") (class "Default")
      (node (ref "IC4") (pin "18") (pinfunction "PB4_18") (pintype "bidirectional"))
    )
    (net (code "277") (name "unconnected-(IC4-PB5-Pad19)") (class "Default")
      (node (ref "IC4") (pin "19") (pinfunction "PB5_19") (pintype "bidirectional"))
    )
    (net (code "278") (name "unconnected-(IC4-PB6-Pad20)") (class "Default")
      (node (ref "IC4") (pin "20") (pinfunction "PB6_20") (pintype "bidirectional"))
    )
    (net (code "279") (name "unconnected-(IC4-PB7-Pad21)") (class "Default")
      (node (ref "IC4") (pin "21") (pinfunction "PB7_21") (pintype "bidirectional"))
    )
    (net (code "280") (name "unconnected-(IC4-PC2-Pad5)") (class "Default")
      (node (ref "IC4") (pin "5") (pinfunction "PC2_5") (pintype "bidirectional"))
    )
    (net (code "281") (name "unconnected-(IC4-PC4-Pad26)") (class "Default")
      (node (ref "IC4") (pin "26") (pinfunction "PC4_26") (pintype "bidirectional"))
    )
    (net (code "282") (name "unconnected-(IC4-PC5-Pad25)") (class "Default")
      (node (ref "IC4") (pin "25") (pinfunction "PC5_25") (pintype "bidirectional"))
    )
    (net (code "283") (name "unconnected-(IC4-PC6-Pad23)") (class "Default")
      (node (ref "IC4") (pin "23") (pinfunction "PC6_23") (pintype "bidirectional"))
    )
    (net (code "284") (name "unconnected-(IC4-PC7-Pad22)") (class "Default")
      (node (ref "IC4") (pin "22") (pinfunction "PC7_22") (pintype "bidirectional"))
    )
    (net (code "285") (name "unconnected-(IC4-PD0-Pad6)") (class "Default")
      (node (ref "IC4") (pin "6") (pinfunction "PD0_6") (pintype "bidirectional"))
    )
    (net (code "286") (name "unconnected-(IC4-PD1-Pad7)") (class "Default")
      (node (ref "IC4") (pin "7") (pinfunction "PD1_7") (pintype "bidirectional"))
    )
    (net (code "287") (name "unconnected-(IC4-PD6-Pad12)") (class "Default")
      (node (ref "IC4") (pin "12") (pinfunction "PD6_12") (pintype "bidirectional"))
    )
    (net (code "288") (name "unconnected-(X6-Pad4)") (class "Default")
      (node (ref "X6") (pin "4") (pinfunction "4_4") (pintype "passive"))
    )
  )
)
